# time-circuits.net
KiCad netlist of a schematic drawn in EAGLE
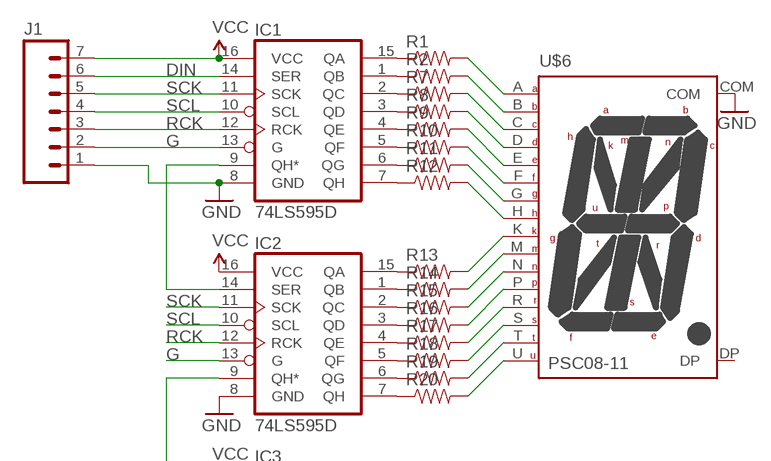
[diagram p0: schematic, sheet 1, part 1 of 2]
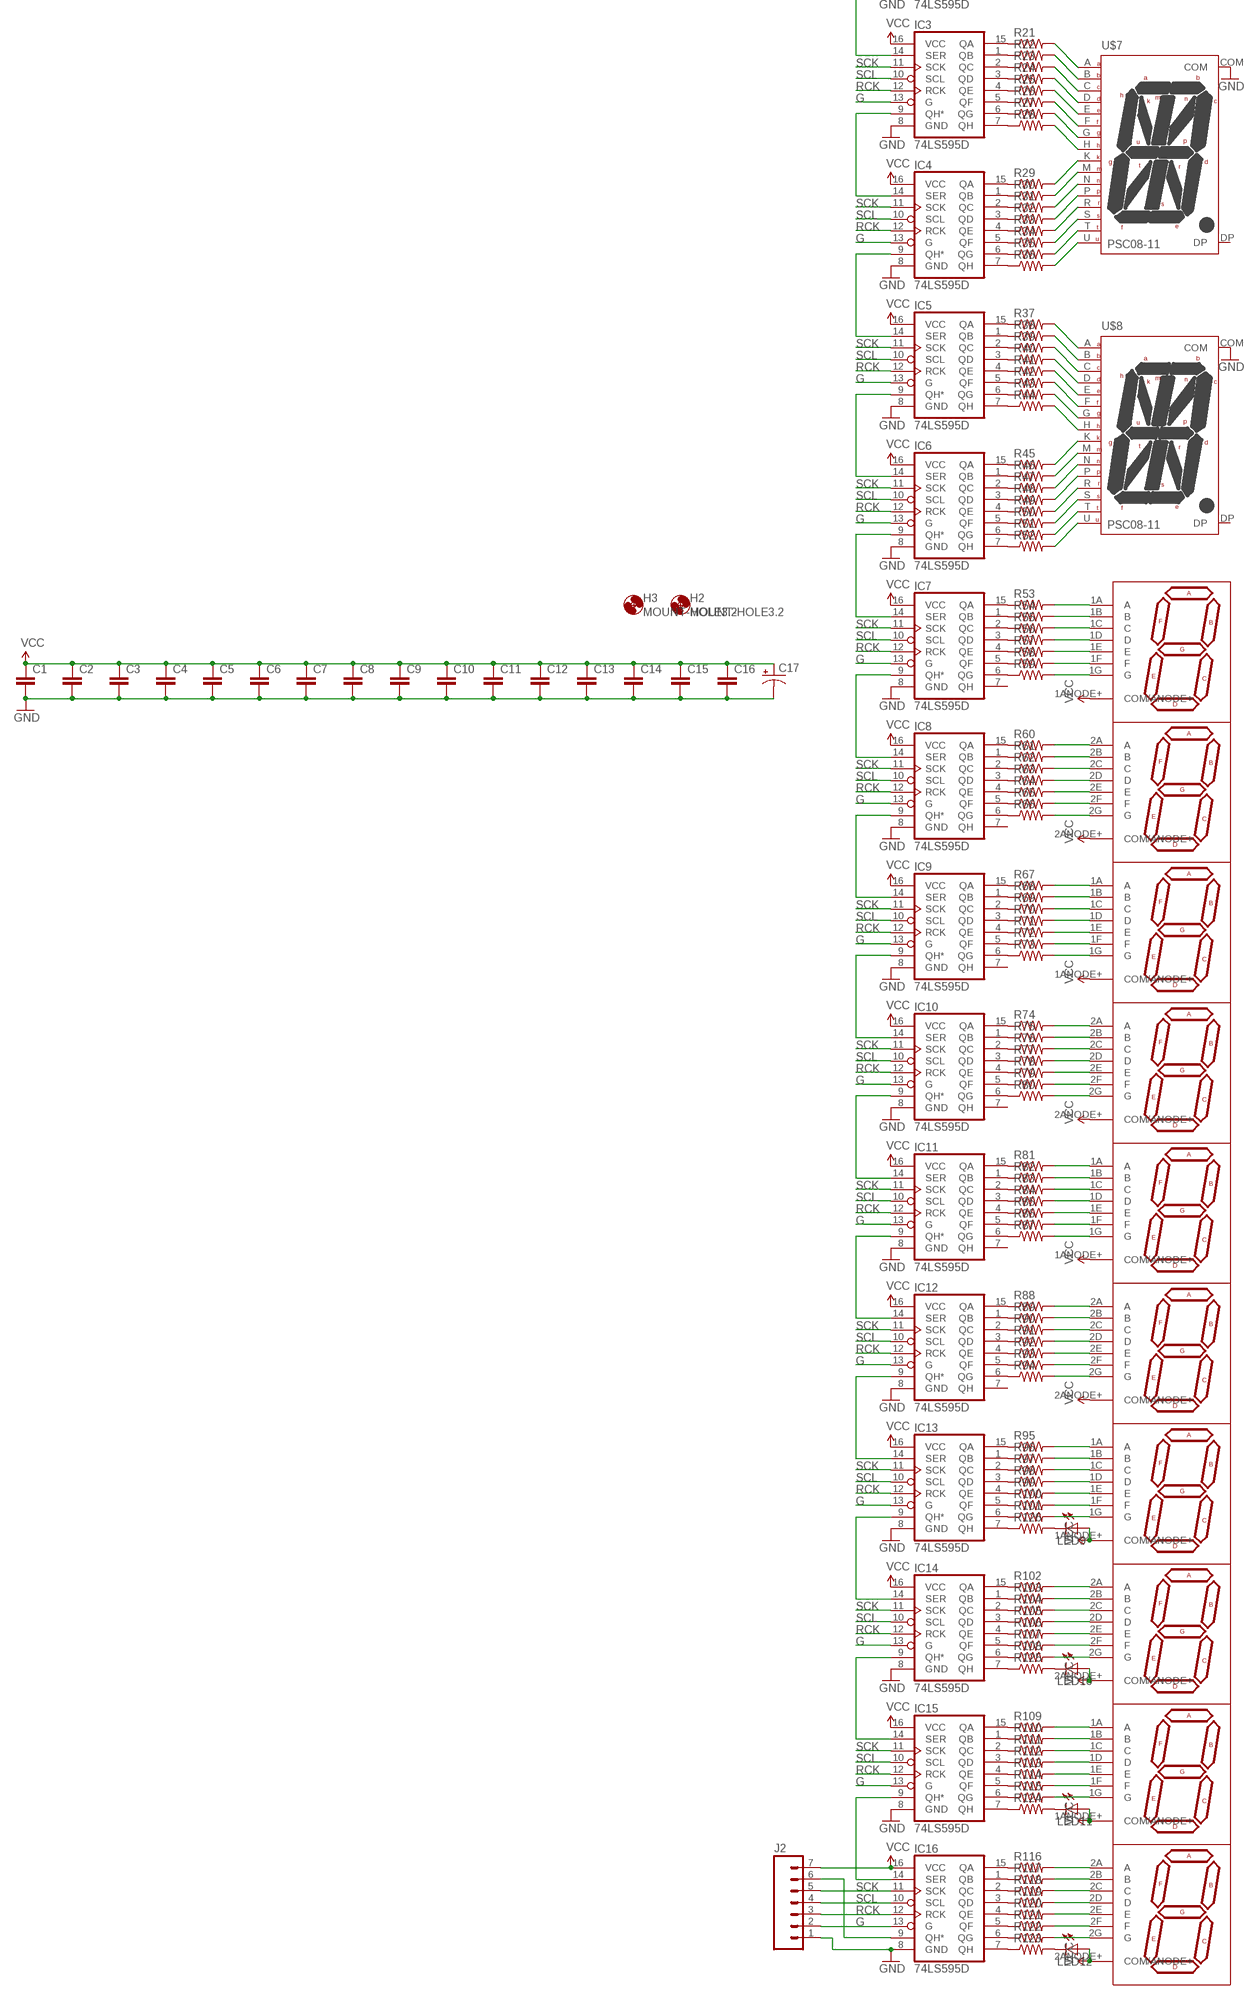
[diagram p1: schematic, sheet 1, part 2 of 2]

(export (version "E")
  (design (tool "Eeschema 10.0.6"))
  (components
    (comp (ref "C1")
      (value "CAP0805")
      (footprint "eagle-import:0805")
      (libsource (lib "eagle-import") (part "CAP0805"))
    )
    (comp (ref "C2")
      (value "CAP0805")
      (footprint "eagle-import:0805")
      (libsource (lib "eagle-import") (part "CAP0805"))
    )
    (comp (ref "C3")
      (value "CAP0805")
      (footprint "eagle-import:0805")
      (libsource (lib "eagle-import") (part "CAP0805"))
    )
    (comp (ref "C4")
      (value "CAP0805")
      (footprint "eagle-import:0805")
      (libsource (lib "eagle-import") (part "CAP0805"))
    )
    (comp (ref "C5")
      (value "CAP0805")
      (footprint "eagle-import:0805")
      (libsource (lib "eagle-import") (part "CAP0805"))
    )
    (comp (ref "C6")
      (value "CAP0805")
      (footprint "eagle-import:0805")
      (libsource (lib "eagle-import") (part "CAP0805"))
    )
    (comp (ref "C7")
      (value "CAP0805")
      (footprint "eagle-import:0805")
      (libsource (lib "eagle-import") (part "CAP0805"))
    )
    (comp (ref "C8")
      (value "CAP0805")
      (footprint "eagle-import:0805")
      (libsource (lib "eagle-import") (part "CAP0805"))
    )
    (comp (ref "C9")
      (value "CAP0805")
      (footprint "eagle-import:0805")
      (libsource (lib "eagle-import") (part "CAP0805"))
    )
    (comp (ref "C10")
      (value "CAP0805")
      (footprint "eagle-import:0805")
      (libsource (lib "eagle-import") (part "CAP0805"))
    )
    (comp (ref "C11")
      (value "CAP0805")
      (footprint "eagle-import:0805")
      (libsource (lib "eagle-import") (part "CAP0805"))
    )
    (comp (ref "C12")
      (value "CAP0805")
      (footprint "eagle-import:0805")
      (libsource (lib "eagle-import") (part "CAP0805"))
    )
    (comp (ref "C13")
      (value "CAP0805")
      (footprint "eagle-import:0805")
      (libsource (lib "eagle-import") (part "CAP0805"))
    )
    (comp (ref "C14")
      (value "CAP0805")
      (footprint "eagle-import:0805")
      (libsource (lib "eagle-import") (part "CAP0805"))
    )
    (comp (ref "C15")
      (value "CAP0805")
      (footprint "eagle-import:0805")
      (libsource (lib "eagle-import") (part "CAP0805"))
    )
    (comp (ref "C16")
      (value "CAP0805")
      (footprint "eagle-import:0805")
      (libsource (lib "eagle-import") (part "CAP0805"))
    )
    (comp (ref "C17")
      (value "CAP_POLH13")
      (footprint "eagle-import:PANASONIC_H13")
      (libsource (lib "eagle-import") (part "CAP_POLH13"))
    )
    (comp (ref "H2")
      (value "MOUNT-HOLE3.2")
      (footprint "eagle-import:3,2")
      (libsource (lib "eagle-import") (part "MOUNT-HOLE3.2"))
    )
    (comp (ref "H3")
      (value "MOUNT-HOLE3.2")
      (footprint "eagle-import:3,2")
      (libsource (lib "eagle-import") (part "MOUNT-HOLE3.2"))
    )
    (comp (ref "IC1")
      (value "74LS595D")
      (footprint "eagle-import:SO16")
      (libsource (lib "eagle-import") (part "74595DLS"))
    )
    (comp (ref "IC2")
      (value "74LS595D")
      (footprint "eagle-import:SO16")
      (libsource (lib "eagle-import") (part "74595DLS"))
    )
    (comp (ref "IC3")
      (value "74LS595D")
      (footprint "eagle-import:SO16")
      (libsource (lib "eagle-import") (part "74595DLS"))
    )
    (comp (ref "IC4")
      (value "74LS595D")
      (footprint "eagle-import:SO16")
      (libsource (lib "eagle-import") (part "74595DLS"))
    )
    (comp (ref "IC5")
      (value "74LS595D")
      (footprint "eagle-import:SO16")
      (libsource (lib "eagle-import") (part "74595DLS"))
    )
    (comp (ref "IC6")
      (value "74LS595D")
      (footprint "eagle-import:SO16")
      (libsource (lib "eagle-import") (part "74595DLS"))
    )
    (comp (ref "IC7")
      (value "74LS595D")
      (footprint "eagle-import:SO16")
      (libsource (lib "eagle-import") (part "74595DLS"))
    )
    (comp (ref "IC8")
      (value "74LS595D")
      (footprint "eagle-import:SO16")
      (libsource (lib "eagle-import") (part "74595DLS"))
    )
    (comp (ref "IC9")
      (value "74LS595D")
      (footprint "eagle-import:SO16")
      (libsource (lib "eagle-import") (part "74595DLS"))
    )
    (comp (ref "IC10")
      (value "74LS595D")
      (footprint "eagle-import:SO16")
      (libsource (lib "eagle-import") (part "74595DLS"))
    )
    (comp (ref "IC11")
      (value "74LS595D")
      (footprint "eagle-import:SO16")
      (libsource (lib "eagle-import") (part "74595DLS"))
    )
    (comp (ref "IC12")
      (value "74LS595D")
      (footprint "eagle-import:SO16")
      (libsource (lib "eagle-import") (part "74595DLS"))
    )
    (comp (ref "IC13")
      (value "74LS595D")
      (footprint "eagle-import:SO16")
      (libsource (lib "eagle-import") (part "74595DLS"))
    )
    (comp (ref "IC14")
      (value "74LS595D")
      (footprint "eagle-import:SO16")
      (libsource (lib "eagle-import") (part "74595DLS"))
    )
    (comp (ref "IC15")
      (value "74LS595D")
      (footprint "eagle-import:SO16")
      (libsource (lib "eagle-import") (part "74595DLS"))
    )
    (comp (ref "IC16")
      (value "74LS595D")
      (footprint "eagle-import:SO16")
      (libsource (lib "eagle-import") (part "74595DLS"))
    )
    (comp (ref "J1")
      (value "M07LOCK")
      (footprint "eagle-import:1X07_LOCK")
      (libsource (lib "eagle-import") (part "M07LOCK"))
    )
    (comp (ref "J2")
      (value "M07LOCK")
      (footprint "eagle-import:1X07_LOCK")
      (libsource (lib "eagle-import") (part "M07LOCK"))
    )
    (comp (ref "LED9")
      (value "LED5MM")
      (footprint "eagle-import:LED5MM")
      (libsource (lib "eagle-import") (part "LED5MM"))
    )
    (comp (ref "LED10")
      (value "LED5MM")
      (footprint "eagle-import:LED5MM")
      (libsource (lib "eagle-import") (part "LED5MM"))
    )
    (comp (ref "LED11")
      (value "LED5MM")
      (footprint "eagle-import:LED5MM")
      (libsource (lib "eagle-import") (part "LED5MM"))
    )
    (comp (ref "LED12")
      (value "LED5MM")
      (footprint "eagle-import:LED5MM")
      (libsource (lib "eagle-import") (part "LED5MM"))
    )
    (comp (ref "R1")
      (value "RESISTOR0805-RES")
      (footprint "eagle-import:0805")
      (libsource (lib "eagle-import") (part "RESISTOR0805-RES"))
    )
    (comp (ref "R2")
      (value "RESISTOR0805-RES")
      (footprint "eagle-import:0805")
      (libsource (lib "eagle-import") (part "RESISTOR0805-RES"))
    )
    (comp (ref "R7")
      (value "RESISTOR0805-RES")
      (footprint "eagle-import:0805")
      (libsource (lib "eagle-import") (part "RESISTOR0805-RES"))
    )
    (comp (ref "R8")
      (value "RESISTOR0805-RES")
      (footprint "eagle-import:0805")
      (libsource (lib "eagle-import") (part "RESISTOR0805-RES"))
    )
    (comp (ref "R9")
      (value "RESISTOR0805-RES")
      (footprint "eagle-import:0805")
      (libsource (lib "eagle-import") (part "RESISTOR0805-RES"))
    )
    (comp (ref "R10")
      (value "RESISTOR0805-RES")
      (footprint "eagle-import:0805")
      (libsource (lib "eagle-import") (part "RESISTOR0805-RES"))
    )
    (comp (ref "R11")
      (value "RESISTOR0805-RES")
      (footprint "eagle-import:0805")
      (libsource (lib "eagle-import") (part "RESISTOR0805-RES"))
    )
    (comp (ref "R12")
      (value "RESISTOR0805-RES")
      (footprint "eagle-import:0805")
      (libsource (lib "eagle-import") (part "RESISTOR0805-RES"))
    )
    (comp (ref "R13")
      (value "RESISTOR0805-RES")
      (footprint "eagle-import:0805")
      (libsource (lib "eagle-import") (part "RESISTOR0805-RES"))
    )
    (comp (ref "R14")
      (value "RESISTOR0805-RES")
      (footprint "eagle-import:0805")
      (libsource (lib "eagle-import") (part "RESISTOR0805-RES"))
    )
    (comp (ref "R15")
      (value "RESISTOR0805-RES")
      (footprint "eagle-import:0805")
      (libsource (lib "eagle-import") (part "RESISTOR0805-RES"))
    )
    (comp (ref "R16")
      (value "RESISTOR0805-RES")
      (footprint "eagle-import:0805")
      (libsource (lib "eagle-import") (part "RESISTOR0805-RES"))
    )
    (comp (ref "R17")
      (value "RESISTOR0805-RES")
      (footprint "eagle-import:0805")
      (libsource (lib "eagle-import") (part "RESISTOR0805-RES"))
    )
    (comp (ref "R18")
      (value "RESISTOR0805-RES")
      (footprint "eagle-import:0805")
      (libsource (lib "eagle-import") (part "RESISTOR0805-RES"))
    )
    (comp (ref "R19")
      (value "RESISTOR0805-RES")
      (footprint "eagle-import:0805")
      (libsource (lib "eagle-import") (part "RESISTOR0805-RES"))
    )
    (comp (ref "R20")
      (value "RESISTOR0805-RES")
      (footprint "eagle-import:0805")
      (libsource (lib "eagle-import") (part "RESISTOR0805-RES"))
    )
    (comp (ref "R21")
      (value "RESISTOR0805-RES")
      (footprint "eagle-import:0805")
      (libsource (lib "eagle-import") (part "RESISTOR0805-RES"))
    )
    (comp (ref "R22")
      (value "RESISTOR0805-RES")
      (footprint "eagle-import:0805")
      (libsource (lib "eagle-import") (part "RESISTOR0805-RES"))
    )
    (comp (ref "R23")
      (value "RESISTOR0805-RES")
      (footprint "eagle-import:0805")
      (libsource (lib "eagle-import") (part "RESISTOR0805-RES"))
    )
    (comp (ref "R24")
      (value "RESISTOR0805-RES")
      (footprint "eagle-import:0805")
      (libsource (lib "eagle-import") (part "RESISTOR0805-RES"))
    )
    (comp (ref "R25")
      (value "RESISTOR0805-RES")
      (footprint "eagle-import:0805")
      (libsource (lib "eagle-import") (part "RESISTOR0805-RES"))
    )
    (comp (ref "R26")
      (value "RESISTOR0805-RES")
      (footprint "eagle-import:0805")
      (libsource (lib "eagle-import") (part "RESISTOR0805-RES"))
    )
    (comp (ref "R27")
      (value "RESISTOR0805-RES")
      (footprint "eagle-import:0805")
      (libsource (lib "eagle-import") (part "RESISTOR0805-RES"))
    )
    (comp (ref "R28")
      (value "RESISTOR0805-RES")
      (footprint "eagle-import:0805")
      (libsource (lib "eagle-import") (part "RESISTOR0805-RES"))
    )
    (comp (ref "R29")
      (value "RESISTOR0805-RES")
      (footprint "eagle-import:0805")
      (libsource (lib "eagle-import") (part "RESISTOR0805-RES"))
    )
    (comp (ref "R30")
      (value "RESISTOR0805-RES")
      (footprint "eagle-import:0805")
      (libsource (lib "eagle-import") (part "RESISTOR0805-RES"))
    )
    (comp (ref "R31")
      (value "RESISTOR0805-RES")
      (footprint "eagle-import:0805")
      (libsource (lib "eagle-import") (part "RESISTOR0805-RES"))
    )
    (comp (ref "R32")
      (value "RESISTOR0805-RES")
      (footprint "eagle-import:0805")
      (libsource (lib "eagle-import") (part "RESISTOR0805-RES"))
    )
    (comp (ref "R33")
      (value "RESISTOR0805-RES")
      (footprint "eagle-import:0805")
      (libsource (lib "eagle-import") (part "RESISTOR0805-RES"))
    )
    (comp (ref "R34")
      (value "RESISTOR0805-RES")
      (footprint "eagle-import:0805")
      (libsource (lib "eagle-import") (part "RESISTOR0805-RES"))
    )
    (comp (ref "R35")
      (value "RESISTOR0805-RES")
      (footprint "eagle-import:0805")
      (libsource (lib "eagle-import") (part "RESISTOR0805-RES"))
    )
    (comp (ref "R36")
      (value "RESISTOR0805-RES")
      (footprint "eagle-import:0805")
      (libsource (lib "eagle-import") (part "RESISTOR0805-RES"))
    )
    (comp (ref "R37")
      (value "RESISTOR0805-RES")
      (footprint "eagle-import:0805")
      (libsource (lib "eagle-import") (part "RESISTOR0805-RES"))
    )
    (comp (ref "R38")
      (value "RESISTOR0805-RES")
      (footprint "eagle-import:0805")
      (libsource (lib "eagle-import") (part "RESISTOR0805-RES"))
    )
    (comp (ref "R39")
      (value "RESISTOR0805-RES")
      (footprint "eagle-import:0805")
      (libsource (lib "eagle-import") (part "RESISTOR0805-RES"))
    )
    (comp (ref "R40")
      (value "RESISTOR0805-RES")
      (footprint "eagle-import:0805")
      (libsource (lib "eagle-import") (part "RESISTOR0805-RES"))
    )
    (comp (ref "R41")
      (value "RESISTOR0805-RES")
      (footprint "eagle-import:0805")
      (libsource (lib "eagle-import") (part "RESISTOR0805-RES"))
    )
    (comp (ref "R42")
      (value "RESISTOR0805-RES")
      (footprint "eagle-import:0805")
      (libsource (lib "eagle-import") (part "RESISTOR0805-RES"))
    )
    (comp (ref "R43")
      (value "RESISTOR0805-RES")
      (footprint "eagle-import:0805")
      (libsource (lib "eagle-import") (part "RESISTOR0805-RES"))
    )
    (comp (ref "R44")
      (value "RESISTOR0805-RES")
      (footprint "eagle-import:0805")
      (libsource (lib "eagle-import") (part "RESISTOR0805-RES"))
    )
    (comp (ref "R45")
      (value "RESISTOR0805-RES")
      (footprint "eagle-import:0805")
      (libsource (lib "eagle-import") (part "RESISTOR0805-RES"))
    )
    (comp (ref "R46")
      (value "RESISTOR0805-RES")
      (footprint "eagle-import:0805")
      (libsource (lib "eagle-import") (part "RESISTOR0805-RES"))
    )
    (comp (ref "R47")
      (value "RESISTOR0805-RES")
      (footprint "eagle-import:0805")
      (libsource (lib "eagle-import") (part "RESISTOR0805-RES"))
    )
    (comp (ref "R48")
      (value "RESISTOR0805-RES")
      (footprint "eagle-import:0805")
      (libsource (lib "eagle-import") (part "RESISTOR0805-RES"))
    )
    (comp (ref "R49")
      (value "RESISTOR0805-RES")
      (footprint "eagle-import:0805")
      (libsource (lib "eagle-import") (part "RESISTOR0805-RES"))
    )
    (comp (ref "R50")
      (value "RESISTOR0805-RES")
      (footprint "eagle-import:0805")
      (libsource (lib "eagle-import") (part "RESISTOR0805-RES"))
    )
    (comp (ref "R51")
      (value "RESISTOR0805-RES")
      (footprint "eagle-import:0805")
      (libsource (lib "eagle-import") (part "RESISTOR0805-RES"))
    )
    (comp (ref "R52")
      (value "RESISTOR0805-RES")
      (footprint "eagle-import:0805")
      (libsource (lib "eagle-import") (part "RESISTOR0805-RES"))
    )
    (comp (ref "R53")
      (value "RESISTOR0805-RES")
      (footprint "eagle-import:0805")
      (libsource (lib "eagle-import") (part "RESISTOR0805-RES"))
    )
    (comp (ref "R54")
      (value "RESISTOR0805-RES")
      (footprint "eagle-import:0805")
      (libsource (lib "eagle-import") (part "RESISTOR0805-RES"))
    )
    (comp (ref "R55")
      (value "RESISTOR0805-RES")
      (footprint "eagle-import:0805")
      (libsource (lib "eagle-import") (part "RESISTOR0805-RES"))
    )
    (comp (ref "R56")
      (value "RESISTOR0805-RES")
      (footprint "eagle-import:0805")
      (libsource (lib "eagle-import") (part "RESISTOR0805-RES"))
    )
    (comp (ref "R57")
      (value "RESISTOR0805-RES")
      (footprint "eagle-import:0805")
      (libsource (lib "eagle-import") (part "RESISTOR0805-RES"))
    )
    (comp (ref "R58")
      (value "RESISTOR0805-RES")
      (footprint "eagle-import:0805")
      (libsource (lib "eagle-import") (part "RESISTOR0805-RES"))
    )
    (comp (ref "R59")
      (value "RESISTOR0805-RES")
      (footprint "eagle-import:0805")
      (libsource (lib "eagle-import") (part "RESISTOR0805-RES"))
    )
    (comp (ref "R60")
      (value "RESISTOR0805-RES")
      (footprint "eagle-import:0805")
      (libsource (lib "eagle-import") (part "RESISTOR0805-RES"))
    )
    (comp (ref "R61")
      (value "RESISTOR0805-RES")
      (footprint "eagle-import:0805")
      (libsource (lib "eagle-import") (part "RESISTOR0805-RES"))
    )
    (comp (ref "R62")
      (value "RESISTOR0805-RES")
      (footprint "eagle-import:0805")
      (libsource (lib "eagle-import") (part "RESISTOR0805-RES"))
    )
    (comp (ref "R63")
      (value "RESISTOR0805-RES")
      (footprint "eagle-import:0805")
      (libsource (lib "eagle-import") (part "RESISTOR0805-RES"))
    )
    (comp (ref "R64")
      (value "RESISTOR0805-RES")
      (footprint "eagle-import:0805")
      (libsource (lib "eagle-import") (part "RESISTOR0805-RES"))
    )
    (comp (ref "R65")
      (value "RESISTOR0805-RES")
      (footprint "eagle-import:0805")
      (libsource (lib "eagle-import") (part "RESISTOR0805-RES"))
    )
    (comp (ref "R66")
      (value "RESISTOR0805-RES")
      (footprint "eagle-import:0805")
      (libsource (lib "eagle-import") (part "RESISTOR0805-RES"))
    )
    (comp (ref "R67")
      (value "RESISTOR0805-RES")
      (footprint "eagle-import:0805")
      (libsource (lib "eagle-import") (part "RESISTOR0805-RES"))
    )
    (comp (ref "R68")
      (value "RESISTOR0805-RES")
      (footprint "eagle-import:0805")
      (libsource (lib "eagle-import") (part "RESISTOR0805-RES"))
    )
    (comp (ref "R69")
      (value "RESISTOR0805-RES")
      (footprint "eagle-import:0805")
      (libsource (lib "eagle-import") (part "RESISTOR0805-RES"))
    )
    (comp (ref "R70")
      (value "RESISTOR0805-RES")
      (footprint "eagle-import:0805")
      (libsource (lib "eagle-import") (part "RESISTOR0805-RES"))
    )
    (comp (ref "R71")
      (value "RESISTOR0805-RES")
      (footprint "eagle-import:0805")
      (libsource (lib "eagle-import") (part "RESISTOR0805-RES"))
    )
    (comp (ref "R72")
      (value "RESISTOR0805-RES")
      (footprint "eagle-import:0805")
      (libsource (lib "eagle-import") (part "RESISTOR0805-RES"))
    )
    (comp (ref "R73")
      (value "RESISTOR0805-RES")
      (footprint "eagle-import:0805")
      (libsource (lib "eagle-import") (part "RESISTOR0805-RES"))
    )
    (comp (ref "R74")
      (value "RESISTOR0805-RES")
      (footprint "eagle-import:0805")
      (libsource (lib "eagle-import") (part "RESISTOR0805-RES"))
    )
    (comp (ref "R75")
      (value "RESISTOR0805-RES")
      (footprint "eagle-import:0805")
      (libsource (lib "eagle-import") (part "RESISTOR0805-RES"))
    )
    (comp (ref "R76")
      (value "RESISTOR0805-RES")
      (footprint "eagle-import:0805")
      (libsource (lib "eagle-import") (part "RESISTOR0805-RES"))
    )
    (comp (ref "R77")
      (value "RESISTOR0805-RES")
      (footprint "eagle-import:0805")
      (libsource (lib "eagle-import") (part "RESISTOR0805-RES"))
    )
    (comp (ref "R78")
      (value "RESISTOR0805-RES")
      (footprint "eagle-import:0805")
      (libsource (lib "eagle-import") (part "RESISTOR0805-RES"))
    )
    (comp (ref "R79")
      (value "RESISTOR0805-RES")
      (footprint "eagle-import:0805")
      (libsource (lib "eagle-import") (part "RESISTOR0805-RES"))
    )
    (comp (ref "R80")
      (value "RESISTOR0805-RES")
      (footprint "eagle-import:0805")
      (libsource (lib "eagle-import") (part "RESISTOR0805-RES"))
    )
    (comp (ref "R81")
      (value "RESISTOR0805-RES")
      (footprint "eagle-import:0805")
      (libsource (lib "eagle-import") (part "RESISTOR0805-RES"))
    )
    (comp (ref "R82")
      (value "RESISTOR0805-RES")
      (footprint "eagle-import:0805")
      (libsource (lib "eagle-import") (part "RESISTOR0805-RES"))
    )
    (comp (ref "R83")
      (value "RESISTOR0805-RES")
      (footprint "eagle-import:0805")
      (libsource (lib "eagle-import") (part "RESISTOR0805-RES"))
    )
    (comp (ref "R84")
      (value "RESISTOR0805-RES")
      (footprint "eagle-import:0805")
      (libsource (lib "eagle-import") (part "RESISTOR0805-RES"))
    )
    (comp (ref "R85")
      (value "RESISTOR0805-RES")
      (footprint "eagle-import:0805")
      (libsource (lib "eagle-import") (part "RESISTOR0805-RES"))
    )
    (comp (ref "R86")
      (value "RESISTOR0805-RES")
      (footprint "eagle-import:0805")
      (libsource (lib "eagle-import") (part "RESISTOR0805-RES"))
    )
    (comp (ref "R87")
      (value "RESISTOR0805-RES")
      (footprint "eagle-import:0805")
      (libsource (lib "eagle-import") (part "RESISTOR0805-RES"))
    )
    (comp (ref "R88")
      (value "RESISTOR0805-RES")
      (footprint "eagle-import:0805")
      (libsource (lib "eagle-import") (part "RESISTOR0805-RES"))
    )
    (comp (ref "R89")
      (value "RESISTOR0805-RES")
      (footprint "eagle-import:0805")
      (libsource (lib "eagle-import") (part "RESISTOR0805-RES"))
    )
    (comp (ref "R90")
      (value "RESISTOR0805-RES")
      (footprint "eagle-import:0805")
      (libsource (lib "eagle-import") (part "RESISTOR0805-RES"))
    )
    (comp (ref "R91")
      (value "RESISTOR0805-RES")
      (footprint "eagle-import:0805")
      (libsource (lib "eagle-import") (part "RESISTOR0805-RES"))
    )
    (comp (ref "R92")
      (value "RESISTOR0805-RES")
      (footprint "eagle-import:0805")
      (libsource (lib "eagle-import") (part "RESISTOR0805-RES"))
    )
    (comp (ref "R93")
      (value "RESISTOR0805-RES")
      (footprint "eagle-import:0805")
      (libsource (lib "eagle-import") (part "RESISTOR0805-RES"))
    )
    (comp (ref "R94")
      (value "RESISTOR0805-RES")
      (footprint "eagle-import:0805")
      (libsource (lib "eagle-import") (part "RESISTOR0805-RES"))
    )
    (comp (ref "R95")
      (value "RESISTOR0805-RES")
      (footprint "eagle-import:0805")
      (libsource (lib "eagle-import") (part "RESISTOR0805-RES"))
    )
    (comp (ref "R96")
      (value "RESISTOR0805-RES")
      (footprint "eagle-import:0805")
      (libsource (lib "eagle-import") (part "RESISTOR0805-RES"))
    )
    (comp (ref "R97")
      (value "RESISTOR0805-RES")
      (footprint "eagle-import:0805")
      (libsource (lib "eagle-import") (part "RESISTOR0805-RES"))
    )
    (comp (ref "R98")
      (value "RESISTOR0805-RES")
      (footprint "eagle-import:0805")
      (libsource (lib "eagle-import") (part "RESISTOR0805-RES"))
    )
    (comp (ref "R99")
      (value "RESISTOR0805-RES")
      (footprint "eagle-import:0805")
      (libsource (lib "eagle-import") (part "RESISTOR0805-RES"))
    )
    (comp (ref "R100")
      (value "RESISTOR0805-RES")
      (footprint "eagle-import:0805")
      (libsource (lib "eagle-import") (part "RESISTOR0805-RES"))
    )
    (comp (ref "R101")
      (value "RESISTOR0805-RES")
      (footprint "eagle-import:0805")
      (libsource (lib "eagle-import") (part "RESISTOR0805-RES"))
    )
    (comp (ref "R102")
      (value "RESISTOR0805-RES")
      (footprint "eagle-import:0805")
      (libsource (lib "eagle-import") (part "RESISTOR0805-RES"))
    )
    (comp (ref "R103")
      (value "RESISTOR0805-RES")
      (footprint "eagle-import:0805")
      (libsource (lib "eagle-import") (part "RESISTOR0805-RES"))
    )
    (comp (ref "R104")
      (value "RESISTOR0805-RES")
      (footprint "eagle-import:0805")
      (libsource (lib "eagle-import") (part "RESISTOR0805-RES"))
    )
    (comp (ref "R105")
      (value "RESISTOR0805-RES")
      (footprint "eagle-import:0805")
      (libsource (lib "eagle-import") (part "RESISTOR0805-RES"))
    )
    (comp (ref "R106")
      (value "RESISTOR0805-RES")
      (footprint "eagle-import:0805")
      (libsource (lib "eagle-import") (part "RESISTOR0805-RES"))
    )
    (comp (ref "R107")
      (value "RESISTOR0805-RES")
      (footprint "eagle-import:0805")
      (libsource (lib "eagle-import") (part "RESISTOR0805-RES"))
    )
    (comp (ref "R108")
      (value "RESISTOR0805-RES")
      (footprint "eagle-import:0805")
      (libsource (lib "eagle-import") (part "RESISTOR0805-RES"))
    )
    (comp (ref "R109")
      (value "RESISTOR0805-RES")
      (footprint "eagle-import:0805")
      (libsource (lib "eagle-import") (part "RESISTOR0805-RES"))
    )
    (comp (ref "R110")
      (value "RESISTOR0805-RES")
      (footprint "eagle-import:0805")
      (libsource (lib "eagle-import") (part "RESISTOR0805-RES"))
    )
    (comp (ref "R111")
      (value "RESISTOR0805-RES")
      (footprint "eagle-import:0805")
      (libsource (lib "eagle-import") (part "RESISTOR0805-RES"))
    )
    (comp (ref "R112")
      (value "RESISTOR0805-RES")
      (footprint "eagle-import:0805")
      (libsource (lib "eagle-import") (part "RESISTOR0805-RES"))
    )
    (comp (ref "R113")
      (value "RESISTOR0805-RES")
      (footprint "eagle-import:0805")
      (libsource (lib "eagle-import") (part "RESISTOR0805-RES"))
    )
    (comp (ref "R114")
      (value "RESISTOR0805-RES")
      (footprint "eagle-import:0805")
      (libsource (lib "eagle-import") (part "RESISTOR0805-RES"))
    )
    (comp (ref "R115")
      (value "RESISTOR0805-RES")
      (footprint "eagle-import:0805")
      (libsource (lib "eagle-import") (part "RESISTOR0805-RES"))
    )
    (comp (ref "R116")
      (value "RESISTOR0805-RES")
      (footprint "eagle-import:0805")
      (libsource (lib "eagle-import") (part "RESISTOR0805-RES"))
    )
    (comp (ref "R117")
      (value "RESISTOR0805-RES")
      (footprint "eagle-import:0805")
      (libsource (lib "eagle-import") (part "RESISTOR0805-RES"))
    )
    (comp (ref "R118")
      (value "RESISTOR0805-RES")
      (footprint "eagle-import:0805")
      (libsource (lib "eagle-import") (part "RESISTOR0805-RES"))
    )
    (comp (ref "R119")
      (value "RESISTOR0805-RES")
      (footprint "eagle-import:0805")
      (libsource (lib "eagle-import") (part "RESISTOR0805-RES"))
    )
    (comp (ref "R120")
      (value "RESISTOR0805-RES")
      (footprint "eagle-import:0805")
      (libsource (lib "eagle-import") (part "RESISTOR0805-RES"))
    )
    (comp (ref "R121")
      (value "RESISTOR0805-RES")
      (footprint "eagle-import:0805")
      (libsource (lib "eagle-import") (part "RESISTOR0805-RES"))
    )
    (comp (ref "R122")
      (value "RESISTOR0805-RES")
      (footprint "eagle-import:0805")
      (libsource (lib "eagle-import") (part "RESISTOR0805-RES"))
    )
    (comp (ref "R123")
      (value "RESISTOR0805-RES")
      (footprint "eagle-import:0805")
      (libsource (lib "eagle-import") (part "RESISTOR0805-RES"))
    )
    (comp (ref "R124")
      (value "RESISTOR0805-RES")
      (footprint "eagle-import:0805")
      (libsource (lib "eagle-import") (part "RESISTOR0805-RES"))
    )
    (comp (ref "R125")
      (value "RESISTOR0805-RES")
      (footprint "eagle-import:0805")
      (libsource (lib "eagle-import") (part "RESISTOR0805-RES"))
    )
    (comp (ref "R126")
      (value "RESISTOR0805-RES")
      (footprint "eagle-import:0805")
      (libsource (lib "eagle-import") (part "RESISTOR0805-RES"))
    )
    (comp (ref "U$1")
      (value "DA08-11")
      (footprint "eagle-import:DA08-11")
      (libsource (lib "eagle-import") (part "DA08-11"))
    )
    (comp (ref "U$2")
      (value "DA08-11")
      (footprint "eagle-import:DA08-11")
      (libsource (lib "eagle-import") (part "DA08-11"))
    )
    (comp (ref "U$3")
      (value "DA08-11")
      (footprint "eagle-import:DA08-11")
      (libsource (lib "eagle-import") (part "DA08-11"))
    )
    (comp (ref "U$4")
      (value "DA08-11")
      (footprint "eagle-import:DA08-11")
      (libsource (lib "eagle-import") (part "DA08-11"))
    )
    (comp (ref "U$5")
      (value "DA08-11")
      (footprint "eagle-import:DA08-11")
      (libsource (lib "eagle-import") (part "DA08-11"))
    )
    (comp (ref "U$6")
      (value "PSC08-11")
      (footprint "eagle-import:PSC08-11")
      (libsource (lib "eagle-import") (part "PSC08-11"))
    )
    (comp (ref "U$7")
      (value "PSC08-11")
      (footprint "eagle-import:PSC08-11")
      (libsource (lib "eagle-import") (part "PSC08-11"))
    )
    (comp (ref "U$8")
      (value "PSC08-11")
      (footprint "eagle-import:PSC08-11")
      (libsource (lib "eagle-import") (part "PSC08-11"))
    )
  )
  (nets
    (net (code "1") (name "/DIN") (class "Default")
      (node (ref "IC1") (pin "14") (pinfunction "SER_14") (pintype "input"))
      (node (ref "J1") (pin "6") (pinfunction "6_6") (pintype "passive"))
    )
    (net (code "2") (name "/G") (class "Default")
      (node (ref "IC1") (pin "13") (pinfunction "G_13") (pintype "input"))
      (node (ref "IC10") (pin "13") (pinfunction "G_13") (pintype "input"))
      (node (ref "IC11") (pin "13") (pinfunction "G_13") (pintype "input"))
      (node (ref "IC12") (pin "13") (pinfunction "G_13") (pintype "input"))
      (node (ref "IC13") (pin "13") (pinfunction "G_13") (pintype "input"))
      (node (ref "IC14") (pin "13") (pinfunction "G_13") (pintype "input"))
      (node (ref "IC15") (pin "13") (pinfunction "G_13") (pintype "input"))
      (node (ref "IC16") (pin "13") (pinfunction "G_13") (pintype "input"))
      (node (ref "IC2") (pin "13") (pinfunction "G_13") (pintype "input"))
      (node (ref "IC3") (pin "13") (pinfunction "G_13") (pintype "input"))
      (node (ref "IC4") (pin "13") (pinfunction "G_13") (pintype "input"))
      (node (ref "IC5") (pin "13") (pinfunction "G_13") (pintype "input"))
      (node (ref "IC6") (pin "13") (pinfunction "G_13") (pintype "input"))
      (node (ref "IC7") (pin "13") (pinfunction "G_13") (pintype "input"))
      (node (ref "IC8") (pin "13") (pinfunction "G_13") (pintype "input"))
      (node (ref "IC9") (pin "13") (pinfunction "G_13") (pintype "input"))
      (node (ref "J1") (pin "2") (pinfunction "2_2") (pintype "passive"))
      (node (ref "J2") (pin "2") (pinfunction "2_2") (pintype "passive"))
    )
    (net (code "3") (name "/RCK") (class "Default")
      (node (ref "IC1") (pin "12") (pinfunction "RCK_12") (pintype "input"))
      (node (ref "IC10") (pin "12") (pinfunction "RCK_12") (pintype "input"))
      (node (ref "IC11") (pin "12") (pinfunction "RCK_12") (pintype "input"))
      (node (ref "IC12") (pin "12") (pinfunction "RCK_12") (pintype "input"))
      (node (ref "IC13") (pin "12") (pinfunction "RCK_12") (pintype "input"))
      (node (ref "IC14") (pin "12") (pinfunction "RCK_12") (pintype "input"))
      (node (ref "IC15") (pin "12") (pinfunction "RCK_12") (pintype "input"))
      (node (ref "IC16") (pin "12") (pinfunction "RCK_12") (pintype "input"))
      (node (ref "IC2") (pin "12") (pinfunction "RCK_12") (pintype "input"))
      (node (ref "IC3") (pin "12") (pinfunction "RCK_12") (pintype "input"))
      (node (ref "IC4") (pin "12") (pinfunction "RCK_12") (pintype "input"))
      (node (ref "IC5") (pin "12") (pinfunction "RCK_12") (pintype "input"))
      (node (ref "IC6") (pin "12") (pinfunction "RCK_12") (pintype "input"))
      (node (ref "IC7") (pin "12") (pinfunction "RCK_12") (pintype "input"))
      (node (ref "IC8") (pin "12") (pinfunction "RCK_12") (pintype "input"))
      (node (ref "IC9") (pin "12") (pinfunction "RCK_12") (pintype "input"))
      (node (ref "J1") (pin "3") (pinfunction "3_3") (pintype "passive"))
      (node (ref "J2") (pin "3") (pinfunction "3_3") (pintype "passive"))
    )
    (net (code "4") (name "/SCK") (class "Default")
      (node (ref "IC1") (pin "11") (pinfunction "SCK_11") (pintype "input"))
      (node (ref "IC10") (pin "11") (pinfunction "SCK_11") (pintype "input"))
      (node (ref "IC11") (pin "11") (pinfunction "SCK_11") (pintype "input"))
      (node (ref "IC12") (pin "11") (pinfunction "SCK_11") (pintype "input"))
      (node (ref "IC13") (pin "11") (pinfunction "SCK_11") (pintype "input"))
      (node (ref "IC14") (pin "11") (pinfunction "SCK_11") (pintype "input"))
      (node (ref "IC15") (pin "11") (pinfunction "SCK_11") (pintype "input"))
      (node (ref "IC16") (pin "11") (pinfunction "SCK_11") (pintype "input"))
      (node (ref "IC2") (pin "11") (pinfunction "SCK_11") (pintype "input"))
      (node (ref "IC3") (pin "11") (pinfunction "SCK_11") (pintype "input"))
      (node (ref "IC4") (pin "11") (pinfunction "SCK_11") (pintype "input"))
      (node (ref "IC5") (pin "11") (pinfunction "SCK_11") (pintype "input"))
      (node (ref "IC6") (pin "11") (pinfunction "SCK_11") (pintype "input"))
      (node (ref "IC7") (pin "11") (pinfunction "SCK_11") (pintype "input"))
      (node (ref "IC8") (pin "11") (pinfunction "SCK_11") (pintype "input"))
      (node (ref "IC9") (pin "11") (pinfunction "SCK_11") (pintype "input"))
      (node (ref "J1") (pin "5") (pinfunction "5_5") (pintype "passive"))
      (node (ref "J2") (pin "5") (pinfunction "5_5") (pintype "passive"))
    )
    (net (code "5") (name "/SCL") (class "Default")
      (node (ref "IC1") (pin "10") (pinfunction "SCL_10") (pintype "input"))
      (node (ref "IC10") (pin "10") (pinfunction "SCL_10") (pintype "input"))
      (node (ref "IC11") (pin "10") (pinfunction "SCL_10") (pintype "input"))
      (node (ref "IC12") (pin "10") (pinfunction "SCL_10") (pintype "input"))
      (node (ref "IC13") (pin "10") (pinfunction "SCL_10") (pintype "input"))
      (node (ref "IC14") (pin "10") (pinfunction "SCL_10") (pintype "input"))
      (node (ref "IC15") (pin "10") (pinfunction "SCL_10") (pintype "input"))
      (node (ref "IC16") (pin "10") (pinfunction "SCL_10") (pintype "input"))
      (node (ref "IC2") (pin "10") (pinfunction "SCL_10") (pintype "input"))
      (node (ref "IC3") (pin "10") (pinfunction "SCL_10") (pintype "input"))
      (node (ref "IC4") (pin "10") (pinfunction "SCL_10") (pintype "input"))
      (node (ref "IC5") (pin "10") (pinfunction "SCL_10") (pintype "input"))
      (node (ref "IC6") (pin "10") (pinfunction "SCL_10") (pintype "input"))
      (node (ref "IC7") (pin "10") (pinfunction "SCL_10") (pintype "input"))
      (node (ref "IC8") (pin "10") (pinfunction "SCL_10") (pintype "input"))
      (node (ref "IC9") (pin "10") (pinfunction "SCL_10") (pintype "input"))
      (node (ref "J1") (pin "4") (pinfunction "4_4") (pintype "passive"))
      (node (ref "J2") (pin "4") (pinfunction "4_4") (pintype "passive"))
    )
    (net (code "6") (name "GND") (class "Default")
      (node (ref "C1") (pin "2") (pinfunction "2_2") (pintype "passive"))
      (node (ref "C10") (pin "2") (pinfunction "2_2") (pintype "passive"))
      (node (ref "C11") (pin "2") (pinfunction "2_2") (pintype "passive"))
      (node (ref "C12") (pin "2") (pinfunction "2_2") (pintype "passive"))
      (node (ref "C13") (pin "2") (pinfunction "2_2") (pintype "passive"))
      (node (ref "C14") (pin "2") (pinfunction "2_2") (pintype "passive"))
      (node (ref "C15") (pin "2") (pinfunction "2_2") (pintype "passive"))
      (node (ref "C16") (pin "2") (pinfunction "2_2") (pintype "passive"))
      (node (ref "C17") (pin "-") (pinfunction "-_-") (pintype "passive"))
      (node (ref "C2") (pin "2") (pinfunction "2_2") (pintype "passive"))
      (node (ref "C3") (pin "2") (pinfunction "2_2") (pintype "passive"))
      (node (ref "C4") (pin "2") (pinfunction "2_2") (pintype "passive"))
      (node (ref "C5") (pin "2") (pinfunction "2_2") (pintype "passive"))
      (node (ref "C6") (pin "2") (pinfunction "2_2") (pintype "passive"))
      (node (ref "C7") (pin "2") (pinfunction "2_2") (pintype "passive"))
      (node (ref "C8") (pin "2") (pinfunction "2_2") (pintype "passive"))
      (node (ref "C9") (pin "2") (pinfunction "2_2") (pintype "passive"))
      (node (ref "IC1") (pin "8") (pinfunction "GND_8") (pintype "power_in"))
      (node (ref "IC10") (pin "8") (pinfunction "GND_8") (pintype "power_in"))
      (node (ref "IC11") (pin "8") (pinfunction "GND_8") (pintype "power_in"))
      (node (ref "IC12") (pin "8") (pinfunction "GND_8") (pintype "power_in"))
      (node (ref "IC13") (pin "8") (pinfunction "GND_8") (pintype "power_in"))
      (node (ref "IC14") (pin "8") (pinfunction "GND_8") (pintype "power_in"))
      (node (ref "IC15") (pin "8") (pinfunction "GND_8") (pintype "power_in"))
      (node (ref "IC16") (pin "8") (pinfunction "GND_8") (pintype "power_in"))
      (node (ref "IC2") (pin "8") (pinfunction "GND_8") (pintype "power_in"))
      (node (ref "IC3") (pin "8") (pinfunction "GND_8") (pintype "power_in"))
      (node (ref "IC4") (pin "8") (pinfunction "GND_8") (pintype "power_in"))
      (node (ref "IC5") (pin "8") (pinfunction "GND_8") (pintype "power_in"))
      (node (ref "IC6") (pin "8") (pinfunction "GND_8") (pintype "power_in"))
      (node (ref "IC7") (pin "8") (pinfunction "GND_8") (pintype "power_in"))
      (node (ref "IC8") (pin "8") (pinfunction "GND_8") (pintype "power_in"))
      (node (ref "IC9") (pin "8") (pinfunction "GND_8") (pintype "power_in"))
      (node (ref "J1") (pin "1") (pinfunction "1_1") (pintype "passive"))
      (node (ref "J2") (pin "1") (pinfunction "1_1") (pintype "passive"))
      (node (ref "U$6") (pin "COM") (pinfunction "COM_COM") (pintype "passive"))
      (node (ref "U$7") (pin "COM") (pinfunction "COM_COM") (pintype "passive"))
      (node (ref "U$8") (pin "COM") (pinfunction "COM_COM") (pintype "passive"))
    )
    (net (code "7") (name "Net-(IC1-QA)") (class "Default")
      (node (ref "IC1") (pin "15") (pinfunction "QA_15") (pintype "tri_state"))
      (node (ref "R1") (pin "1") (pinfunction "1_1") (pintype "passive"))
    )
    (net (code "8") (name "Net-(IC1-QB)") (class "Default")
      (node (ref "IC1") (pin "1") (pinfunction "QB_1") (pintype "tri_state"))
      (node (ref "R2") (pin "1") (pinfunction "1_1") (pintype "passive"))
    )
    (net (code "9") (name "Net-(IC1-QC)") (class "Default")
      (node (ref "IC1") (pin "2") (pinfunction "QC_2") (pintype "tri_state"))
      (node (ref "R7") (pin "1") (pinfunction "1_1") (pintype "passive"))
    )
    (net (code "10") (name "Net-(IC1-QD)") (class "Default")
      (node (ref "IC1") (pin "3") (pinfunction "QD_3") (pintype "tri_state"))
      (node (ref "R8") (pin "1") (pinfunction "1_1") (pintype "passive"))
    )
    (net (code "11") (name "Net-(IC1-QE)") (class "Default")
      (node (ref "IC1") (pin "4") (pinfunction "QE_4") (pintype "tri_state"))
      (node (ref "R9") (pin "1") (pinfunction "1_1") (pintype "passive"))
    )
    (net (code "12") (name "Net-(IC1-QF)") (class "Default")
      (node (ref "IC1") (pin "5") (pinfunction "QF_5") (pintype "tri_state"))
      (node (ref "R10") (pin "1") (pinfunction "1_1") (pintype "passive"))
    )
    (net (code "13") (name "Net-(IC1-QG)") (class "Default")
      (node (ref "IC1") (pin "6") (pinfunction "QG_6") (pintype "tri_state"))
      (node (ref "R11") (pin "1") (pinfunction "1_1") (pintype "passive"))
    )
    (net (code "14") (name "Net-(IC1-QH)") (class "Default")
      (node (ref "IC1") (pin "7") (pinfunction "QH_7") (pintype "tri_state"))
      (node (ref "R12") (pin "1") (pinfunction "1_1") (pintype "passive"))
    )
    (net (code "15") (name "Net-(IC1-QH*)") (class "Default")
      (node (ref "IC1") (pin "9") (pinfunction "QH*_9") (pintype "tri_state"))
      (node (ref "IC2") (pin "14") (pinfunction "SER_14") (pintype "input"))
    )
    (net (code "16") (name "Net-(IC2-QA)") (class "Default")
      (node (ref "IC2") (pin "15") (pinfunction "QA_15") (pintype "tri_state"))
      (node (ref "R13") (pin "1") (pinfunction "1_1") (pintype "passive"))
    )
    (net (code "17") (name "Net-(IC2-QB)") (class "Default")
      (node (ref "IC2") (pin "1") (pinfunction "QB_1") (pintype "tri_state"))
      (node (ref "R14") (pin "1") (pinfunction "1_1") (pintype "passive"))
    )
    (net (code "18") (name "Net-(IC2-QC)") (class "Default")
      (node (ref "IC2") (pin "2") (pinfunction "QC_2") (pintype "tri_state"))
      (node (ref "R15") (pin "1") (pinfunction "1_1") (pintype "passive"))
    )
    (net (code "19") (name "Net-(IC2-QD)") (class "Default")
      (node (ref "IC2") (pin "3") (pinfunction "QD_3") (pintype "tri_state"))
      (node (ref "R16") (pin "1") (pinfunction "1_1") (pintype "passive"))
    )
    (net (code "20") (name "Net-(IC2-QE)") (class "Default")
      (node (ref "IC2") (pin "4") (pinfunction "QE_4") (pintype "tri_state"))
      (node (ref "R17") (pin "1") (pinfunction "1_1") (pintype "passive"))
    )
    (net (code "21") (name "Net-(IC2-QF)") (class "Default")
      (node (ref "IC2") (pin "5") (pinfunction "QF_5") (pintype "tri_state"))
      (node (ref "R18") (pin "1") (pinfunction "1_1") (pintype "passive"))
    )
    (net (code "22") (name "Net-(IC2-QG)") (class "Default")
      (node (ref "IC2") (pin "6") (pinfunction "QG_6") (pintype "tri_state"))
      (node (ref "R19") (pin "1") (pinfunction "1_1") (pintype "passive"))
    )
    (net (code "23") (name "Net-(IC2-QH)") (class "Default")
      (node (ref "IC2") (pin "7") (pinfunction "QH_7") (pintype "tri_state"))
      (node (ref "R20") (pin "1") (pinfunction "1_1") (pintype "passive"))
    )
    (net (code "24") (name "Net-(IC2-QH*)") (class "Default")
      (node (ref "IC2") (pin "9") (pinfunction "QH*_9") (pintype "tri_state"))
      (node (ref "IC3") (pin "14") (pinfunction "SER_14") (pintype "input"))
    )
    (net (code "25") (name "Net-(IC3-QA)") (class "Default")
      (node (ref "IC3") (pin "15") (pinfunction "QA_15") (pintype "tri_state"))
      (node (ref "R21") (pin "1") (pinfunction "1_1") (pintype "passive"))
    )
    (net (code "26") (name "Net-(IC3-QB)") (class "Default")
      (node (ref "IC3") (pin "1") (pinfunction "QB_1") (pintype "tri_state"))
      (node (ref "R22") (pin "1") (pinfunction "1_1") (pintype "passive"))
    )
    (net (code "27") (name "Net-(IC3-QC)") (class "Default")
      (node (ref "IC3") (pin "2") (pinfunction "QC_2") (pintype "tri_state"))
      (node (ref "R23") (pin "1") (pinfunction "1_1") (pintype "passive"))
    )
    (net (code "28") (name "Net-(IC3-QD)") (class "Default")
      (node (ref "IC3") (pin "3") (pinfunction "QD_3") (pintype "tri_state"))
      (node (ref "R24") (pin "1") (pinfunction "1_1") (pintype "passive"))
    )
    (net (code "29") (name "Net-(IC3-QE)") (class "Default")
      (node (ref "IC3") (pin "4") (pinfunction "QE_4") (pintype "tri_state"))
      (node (ref "R25") (pin "1") (pinfunction "1_1") (pintype "passive"))
    )
    (net (code "30") (name "Net-(IC3-QF)") (class "Default")
      (node (ref "IC3") (pin "5") (pinfunction "QF_5") (pintype "tri_state"))
      (node (ref "R26") (pin "1") (pinfunction "1_1") (pintype "passive"))
    )
    (net (code "31") (name "Net-(IC3-QG)") (class "Default")
      (node (ref "IC3") (pin "6") (pinfunction "QG_6") (pintype "tri_state"))
      (node (ref "R27") (pin "1") (pinfunction "1_1") (pintype "passive"))
    )
    (net (code "32") (name "Net-(IC3-QH)") (class "Default")
      (node (ref "IC3") (pin "7") (pinfunction "QH_7") (pintype "tri_state"))
      (node (ref "R28") (pin "1") (pinfunction "1_1") (pintype "passive"))
    )
    (net (code "33") (name "Net-(IC3-QH*)") (class "Default")
      (node (ref "IC3") (pin "9") (pinfunction "QH*_9") (pintype "tri_state"))
      (node (ref "IC4") (pin "14") (pinfunction "SER_14") (pintype "input"))
    )
    (net (code "34") (name "Net-(IC4-QA)") (class "Default")
      (node (ref "IC4") (pin "15") (pinfunction "QA_15") (pintype "tri_state"))
      (node (ref "R29") (pin "1") (pinfunction "1_1") (pintype "passive"))
    )
    (net (code "35") (name "Net-(IC4-QB)") (class "Default")
      (node (ref "IC4") (pin "1") (pinfunction "QB_1") (pintype "tri_state"))
      (node (ref "R30") (pin "1") (pinfunction "1_1") (pintype "passive"))
    )
    (net (code "36") (name "Net-(IC4-QC)") (class "Default")
      (node (ref "IC4") (pin "2") (pinfunction "QC_2") (pintype "tri_state"))
      (node (ref "R31") (pin "1") (pinfunction "1_1") (pintype "passive"))
    )
    (net (code "37") (name "Net-(IC4-QD)") (class "Default")
      (node (ref "IC4") (pin "3") (pinfunction "QD_3") (pintype "tri_state"))
      (node (ref "R32") (pin "1") (pinfunction "1_1") (pintype "passive"))
    )
    (net (code "38") (name "Net-(IC4-QE)") (class "Default")
      (node (ref "IC4") (pin "4") (pinfunction "QE_4") (pintype "tri_state"))
      (node (ref "R33") (pin "1") (pinfunction "1_1") (pintype "passive"))
    )
    (net (code "39") (name "Net-(IC4-QF)") (class "Default")
      (node (ref "IC4") (pin "5") (pinfunction "QF_5") (pintype "tri_state"))
      (node (ref "R34") (pin "1") (pinfunction "1_1") (pintype "passive"))
    )
    (net (code "40") (name "Net-(IC4-QG)") (class "Default")
      (node (ref "IC4") (pin "6") (pinfunction "QG_6") (pintype "tri_state"))
      (node (ref "R35") (pin "1") (pinfunction "1_1") (pintype "passive"))
    )
    (net (code "41") (name "Net-(IC4-QH)") (class "Default")
      (node (ref "IC4") (pin "7") (pinfunction "QH_7") (pintype "tri_state"))
      (node (ref "R36") (pin "1") (pinfunction "1_1") (pintype "passive"))
    )
    (net (code "42") (name "Net-(IC4-QH*)") (class "Default")
      (node (ref "IC4") (pin "9") (pinfunction "QH*_9") (pintype "tri_state"))
      (node (ref "IC5") (pin "14") (pinfunction "SER_14") (pintype "input"))
    )
    (net (code "43") (name "Net-(IC5-QA)") (class "Default")
      (node (ref "IC5") (pin "15") (pinfunction "QA_15") (pintype "tri_state"))
      (node (ref "R37") (pin "1") (pinfunction "1_1") (pintype "passive"))
    )
    (net (code "44") (name "Net-(IC5-QB)") (class "Default")
      (node (ref "IC5") (pin "1") (pinfunction "QB_1") (pintype "tri_state"))
      (node (ref "R38") (pin "1") (pinfunction "1_1") (pintype "passive"))
    )
    (net (code "45") (name "Net-(IC5-QC)") (class "Default")
      (node (ref "IC5") (pin "2") (pinfunction "QC_2") (pintype "tri_state"))
      (node (ref "R39") (pin "1") (pinfunction "1_1") (pintype "passive"))
    )
    (net (code "46") (name "Net-(IC5-QD)") (class "Default")
      (node (ref "IC5") (pin "3") (pinfunction "QD_3") (pintype "tri_state"))
      (node (ref "R40") (pin "1") (pinfunction "1_1") (pintype "passive"))
    )
    (net (code "47") (name "Net-(IC5-QE)") (class "Default")
      (node (ref "IC5") (pin "4") (pinfunction "QE_4") (pintype "tri_state"))
      (node (ref "R41") (pin "1") (pinfunction "1_1") (pintype "passive"))
    )
    (net (code "48") (name "Net-(IC5-QF)") (class "Default")
      (node (ref "IC5") (pin "5") (pinfunction "QF_5") (pintype "tri_state"))
      (node (ref "R42") (pin "1") (pinfunction "1_1") (pintype "passive"))
    )
    (net (code "49") (name "Net-(IC5-QG)") (class "Default")
      (node (ref "IC5") (pin "6") (pinfunction "QG_6") (pintype "tri_state"))
      (node (ref "R43") (pin "1") (pinfunction "1_1") (pintype "passive"))
    )
    (net (code "50") (name "Net-(IC5-QH)") (class "Default")
      (node (ref "IC5") (pin "7") (pinfunction "QH_7") (pintype "tri_state"))
      (node (ref "R44") (pin "1") (pinfunction "1_1") (pintype "passive"))
    )
    (net (code "51") (name "Net-(IC5-QH*)") (class "Default")
      (node (ref "IC5") (pin "9") (pinfunction "QH*_9") (pintype "tri_state"))
      (node (ref "IC6") (pin "14") (pinfunction "SER_14") (pintype "input"))
    )
    (net (code "52") (name "Net-(IC6-QA)") (class "Default")
      (node (ref "IC6") (pin "15") (pinfunction "QA_15") (pintype "tri_state"))
      (node (ref "R45") (pin "1") (pinfunction "1_1") (pintype "passive"))
    )
    (net (code "53") (name "Net-(IC6-QB)") (class "Default")
      (node (ref "IC6") (pin "1") (pinfunction "QB_1") (pintype "tri_state"))
      (node (ref "R46") (pin "1") (pinfunction "1_1") (pintype "passive"))
    )
    (net (code "54") (name "Net-(IC6-QC)") (class "Default")
      (node (ref "IC6") (pin "2") (pinfunction "QC_2") (pintype "tri_state"))
      (node (ref "R47") (pin "1") (pinfunction "1_1") (pintype "passive"))
    )
    (net (code "55") (name "Net-(IC6-QD)") (class "Default")
      (node (ref "IC6") (pin "3") (pinfunction "QD_3") (pintype "tri_state"))
      (node (ref "R48") (pin "1") (pinfunction "1_1") (pintype "passive"))
    )
    (net (code "56") (name "Net-(IC6-QE)") (class "Default")
      (node (ref "IC6") (pin "4") (pinfunction "QE_4") (pintype "tri_state"))
      (node (ref "R49") (pin "1") (pinfunction "1_1") (pintype "passive"))
    )
    (net (code "57") (name "Net-(IC6-QF)") (class "Default")
      (node (ref "IC6") (pin "5") (pinfunction "QF_5") (pintype "tri_state"))
      (node (ref "R50") (pin "1") (pinfunction "1_1") (pintype "passive"))
    )
    (net (code "58") (name "Net-(IC6-QG)") (class "Default")
      (node (ref "IC6") (pin "6") (pinfunction "QG_6") (pintype "tri_state"))
      (node (ref "R51") (pin "1") (pinfunction "1_1") (pintype "passive"))
    )
    (net (code "59") (name "Net-(IC6-QH)") (class "Default")
      (node (ref "IC6") (pin "7") (pinfunction "QH_7") (pintype "tri_state"))
      (node (ref "R52") (pin "1") (pinfunction "1_1") (pintype "passive"))
    )
    (net (code "60") (name "Net-(IC6-QH*)") (class "Default")
      (node (ref "IC6") (pin "9") (pinfunction "QH*_9") (pintype "tri_state"))
      (node (ref "IC7") (pin "14") (pinfunction "SER_14") (pintype "input"))
    )
    (net (code "61") (name "Net-(IC7-QA)") (class "Default")
      (node (ref "IC7") (pin "15") (pinfunction "QA_15") (pintype "tri_state"))
      (node (ref "R53") (pin "1") (pinfunction "1_1") (pintype "passive"))
    )
    (net (code "62") (name "Net-(IC7-QB)") (class "Default")
      (node (ref "IC7") (pin "1") (pinfunction "QB_1") (pintype "tri_state"))
      (node (ref "R54") (pin "1") (pinfunction "1_1") (pintype "passive"))
    )
    (net (code "63") (name "Net-(IC7-QC)") (class "Default")
      (node (ref "IC7") (pin "2") (pinfunction "QC_2") (pintype "tri_state"))
      (node (ref "R55") (pin "1") (pinfunction "1_1") (pintype "passive"))
    )
    (net (code "64") (name "Net-(IC7-QD)") (class "Default")
      (node (ref "IC7") (pin "3") (pinfunction "QD_3") (pintype "tri_state"))
      (node (ref "R56") (pin "1") (pinfunction "1_1") (pintype "passive"))
    )
    (net (code "65") (name "Net-(IC7-QE)") (class "Default")
      (node (ref "IC7") (pin "4") (pinfunction "QE_4") (pintype "tri_state"))
      (node (ref "R57") (pin "1") (pinfunction "1_1") (pintype "passive"))
    )
    (net (code "66") (name "Net-(IC7-QF)") (class "Default")
      (node (ref "IC7") (pin "5") (pinfunction "QF_5") (pintype "tri_state"))
      (node (ref "R58") (pin "1") (pinfunction "1_1") (pintype "passive"))
    )
    (net (code "67") (name "Net-(IC7-QG)") (class "Default")
      (node (ref "IC7") (pin "6") (pinfunction "QG_6") (pintype "tri_state"))
      (node (ref "R59") (pin "1") (pinfunction "1_1") (pintype "passive"))
    )
    (net (code "68") (name "Net-(IC7-QH*)") (class "Default")
      (node (ref "IC7") (pin "9") (pinfunction "QH*_9") (pintype "tri_state"))
      (node (ref "IC8") (pin "14") (pinfunction "SER_14") (pintype "input"))
    )
    (net (code "69") (name "Net-(IC8-QA)") (class "Default")
      (node (ref "IC8") (pin "15") (pinfunction "QA_15") (pintype "tri_state"))
      (node (ref "R60") (pin "1") (pinfunction "1_1") (pintype "passive"))
    )
    (net (code "70") (name "Net-(IC8-QB)") (class "Default")
      (node (ref "IC8") (pin "1") (pinfunction "QB_1") (pintype "tri_state"))
      (node (ref "R61") (pin "1") (pinfunction "1_1") (pintype "passive"))
    )
    (net (code "71") (name "Net-(IC8-QC)") (class "Default")
      (node (ref "IC8") (pin "2") (pinfunction "QC_2") (pintype "tri_state"))
      (node (ref "R62") (pin "1") (pinfunction "1_1") (pintype "passive"))
    )
    (net (code "72") (name "Net-(IC8-QD)") (class "Default")
      (node (ref "IC8") (pin "3") (pinfunction "QD_3") (pintype "tri_state"))
      (node (ref "R63") (pin "1") (pinfunction "1_1") (pintype "passive"))
    )
    (net (code "73") (name "Net-(IC8-QE)") (class "Default")
      (node (ref "IC8") (pin "4") (pinfunction "QE_4") (pintype "tri_state"))
      (node (ref "R64") (pin "1") (pinfunction "1_1") (pintype "passive"))
    )
    (net (code "74") (name "Net-(IC8-QF)") (class "Default")
      (node (ref "IC8") (pin "5") (pinfunction "QF_5") (pintype "tri_state"))
      (node (ref "R65") (pin "1") (pinfunction "1_1") (pintype "passive"))
    )
    (net (code "75") (name "Net-(IC8-QG)") (class "Default")
      (node (ref "IC8") (pin "6") (pinfunction "QG_6") (pintype "tri_state"))
      (node (ref "R66") (pin "1") (pinfunction "1_1") (pintype "passive"))
    )
    (net (code "76") (name "Net-(IC8-QH*)") (class "Default")
      (node (ref "IC8") (pin "9") (pinfunction "QH*_9") (pintype "tri_state"))
      (node (ref "IC9") (pin "14") (pinfunction "SER_14") (pintype "input"))
    )
    (net (code "77") (name "Net-(IC9-QA)") (class "Default")
      (node (ref "IC9") (pin "15") (pinfunction "QA_15") (pintype "tri_state"))
      (node (ref "R67") (pin "1") (pinfunction "1_1") (pintype "passive"))
    )
    (net (code "78") (name "Net-(IC9-QB)") (class "Default")
      (node (ref "IC9") (pin "1") (pinfunction "QB_1") (pintype "tri_state"))
      (node (ref "R68") (pin "1") (pinfunction "1_1") (pintype "passive"))
    )
    (net (code "79") (name "Net-(IC9-QC)") (class "Default")
      (node (ref "IC9") (pin "2") (pinfunction "QC_2") (pintype "tri_state"))
      (node (ref "R69") (pin "1") (pinfunction "1_1") (pintype "passive"))
    )
    (net (code "80") (name "Net-(IC9-QD)") (class "Default")
      (node (ref "IC9") (pin "3") (pinfunction "QD_3") (pintype "tri_state"))
      (node (ref "R70") (pin "1") (pinfunction "1_1") (pintype "passive"))
    )
    (net (code "81") (name "Net-(IC9-QE)") (class "Default")
      (node (ref "IC9") (pin "4") (pinfunction "QE_4") (pintype "tri_state"))
      (node (ref "R71") (pin "1") (pinfunction "1_1") (pintype "passive"))
    )
    (net (code "82") (name "Net-(IC9-QF)") (class "Default")
      (node (ref "IC9") (pin "5") (pinfunction "QF_5") (pintype "tri_state"))
      (node (ref "R72") (pin "1") (pinfunction "1_1") (pintype "passive"))
    )
    (net (code "83") (name "Net-(IC9-QG)") (class "Default")
      (node (ref "IC9") (pin "6") (pinfunction "QG_6") (pintype "tri_state"))
      (node (ref "R73") (pin "1") (pinfunction "1_1") (pintype "passive"))
    )
    (net (code "84") (name "Net-(IC10-QA)") (class "Default")
      (node (ref "IC10") (pin "15") (pinfunction "QA_15") (pintype "tri_state"))
      (node (ref "R74") (pin "1") (pinfunction "1_1") (pintype "passive"))
    )
    (net (code "85") (name "Net-(IC10-QB)") (class "Default")
      (node (ref "IC10") (pin "1") (pinfunction "QB_1") (pintype "tri_state"))
      (node (ref "R75") (pin "1") (pinfunction "1_1") (pintype "passive"))
    )
    (net (code "86") (name "Net-(IC10-QC)") (class "Default")
      (node (ref "IC10") (pin "2") (pinfunction "QC_2") (pintype "tri_state"))
      (node (ref "R76") (pin "1") (pinfunction "1_1") (pintype "passive"))
    )
    (net (code "87") (name "Net-(IC10-QD)") (class "Default")
      (node (ref "IC10") (pin "3") (pinfunction "QD_3") (pintype "tri_state"))
      (node (ref "R77") (pin "1") (pinfunction "1_1") (pintype "passive"))
    )
    (net (code "88") (name "Net-(IC10-QE)") (class "Default")
      (node (ref "IC10") (pin "4") (pinfunction "QE_4") (pintype "tri_state"))
      (node (ref "R78") (pin "1") (pinfunction "1_1") (pintype "passive"))
    )
    (net (code "89") (name "Net-(IC10-QF)") (class "Default")
      (node (ref "IC10") (pin "5") (pinfunction "QF_5") (pintype "tri_state"))
      (node (ref "R79") (pin "1") (pinfunction "1_1") (pintype "passive"))
    )
    (net (code "90") (name "Net-(IC10-QG)") (class "Default")
      (node (ref "IC10") (pin "6") (pinfunction "QG_6") (pintype "tri_state"))
      (node (ref "R80") (pin "1") (pinfunction "1_1") (pintype "passive"))
    )
    (net (code "91") (name "Net-(IC10-QH*)") (class "Default")
      (node (ref "IC10") (pin "9") (pinfunction "QH*_9") (pintype "tri_state"))
      (node (ref "IC11") (pin "14") (pinfunction "SER_14") (pintype "input"))
    )
    (net (code "92") (name "Net-(IC10-SER)") (class "Default")
      (node (ref "IC10") (pin "14") (pinfunction "SER_14") (pintype "input"))
      (node (ref "IC9") (pin "9") (pinfunction "QH*_9") (pintype "tri_state"))
    )
    (net (code "93") (name "Net-(IC11-QA)") (class "Default")
      (node (ref "IC11") (pin "15") (pinfunction "QA_15") (pintype "tri_state"))
      (node (ref "R81") (pin "1") (pinfunction "1_1") (pintype "passive"))
    )
    (net (code "94") (name "Net-(IC11-QB)") (class "Default")
      (node (ref "IC11") (pin "1") (pinfunction "QB_1") (pintype "tri_state"))
      (node (ref "R82") (pin "1") (pinfunction "1_1") (pintype "passive"))
    )
    (net (code "95") (name "Net-(IC11-QC)") (class "Default")
      (node (ref "IC11") (pin "2") (pinfunction "QC_2") (pintype "tri_state"))
      (node (ref "R83") (pin "1") (pinfunction "1_1") (pintype "passive"))
    )
    (net (code "96") (name "Net-(IC11-QD)") (class "Default")
      (node (ref "IC11") (pin "3") (pinfunction "QD_3") (pintype "tri_state"))
      (node (ref "R84") (pin "1") (pinfunction "1_1") (pintype "passive"))
    )
    (net (code "97") (name "Net-(IC11-QE)") (class "Default")
      (node (ref "IC11") (pin "4") (pinfunction "QE_4") (pintype "tri_state"))
      (node (ref "R85") (pin "1") (pinfunction "1_1") (pintype "passive"))
    )
    (net (code "98") (name "Net-(IC11-QF)") (class "Default")
      (node (ref "IC11") (pin "5") (pinfunction "QF_5") (pintype "tri_state"))
      (node (ref "R86") (pin "1") (pinfunction "1_1") (pintype "passive"))
    )
    (net (code "99") (name "Net-(IC11-QG)") (class "Default")
      (node (ref "IC11") (pin "6") (pinfunction "QG_6") (pintype "tri_state"))
      (node (ref "R87") (pin "1") (pinfunction "1_1") (pintype "passive"))
    )
    (net (code "100") (name "Net-(IC11-QH*)") (class "Default")
      (node (ref "IC11") (pin "9") (pinfunction "QH*_9") (pintype "tri_state"))
      (node (ref "IC12") (pin "14") (pinfunction "SER_14") (pintype "input"))
    )
    (net (code "101") (name "Net-(IC12-QA)") (class "Default")
      (node (ref "IC12") (pin "15") (pinfunction "QA_15") (pintype "tri_state"))
      (node (ref "R88") (pin "1") (pinfunction "1_1") (pintype "passive"))
    )
    (net (code "102") (name "Net-(IC12-QB)") (class "Default")
      (node (ref "IC12") (pin "1") (pinfunction "QB_1") (pintype "tri_state"))
      (node (ref "R89") (pin "1") (pinfunction "1_1") (pintype "passive"))
    )
    (net (code "103") (name "Net-(IC12-QC)") (class "Default")
      (node (ref "IC12") (pin "2") (pinfunction "QC_2") (pintype "tri_state"))
      (node (ref "R90") (pin "1") (pinfunction "1_1") (pintype "passive"))
    )
    (net (code "104") (name "Net-(IC12-QD)") (class "Default")
      (node (ref "IC12") (pin "3") (pinfunction "QD_3") (pintype "tri_state"))
      (node (ref "R91") (pin "1") (pinfunction "1_1") (pintype "passive"))
    )
    (net (code "105") (name "Net-(IC12-QE)") (class "Default")
      (node (ref "IC12") (pin "4") (pinfunction "QE_4") (pintype "tri_state"))
      (node (ref "R92") (pin "1") (pinfunction "1_1") (pintype "passive"))
    )
    (net (code "106") (name "Net-(IC12-QF)") (class "Default")
      (node (ref "IC12") (pin "5") (pinfunction "QF_5") (pintype "tri_state"))
      (node (ref "R93") (pin "1") (pinfunction "1_1") (pintype "passive"))
    )
    (net (code "107") (name "Net-(IC12-QG)") (class "Default")
      (node (ref "IC12") (pin "6") (pinfunction "QG_6") (pintype "tri_state"))
      (node (ref "R94") (pin "1") (pinfunction "1_1") (pintype "passive"))
    )
    (net (code "108") (name "Net-(IC12-QH*)") (class "Default")
      (node (ref "IC12") (pin "9") (pinfunction "QH*_9") (pintype "tri_state"))
      (node (ref "IC13") (pin "14") (pinfunction "SER_14") (pintype "input"))
    )
    (net (code "109") (name "Net-(IC13-QA)") (class "Default")
      (node (ref "IC13") (pin "15") (pinfunction "QA_15") (pintype "tri_state"))
      (node (ref "R95") (pin "1") (pinfunction "1_1") (pintype "passive"))
    )
    (net (code "110") (name "Net-(IC13-QB)") (class "Default")
      (node (ref "IC13") (pin "1") (pinfunction "QB_1") (pintype "tri_state"))
      (node (ref "R96") (pin "1") (pinfunction "1_1") (pintype "passive"))
    )
    (net (code "111") (name "Net-(IC13-QC)") (class "Default")
      (node (ref "IC13") (pin "2") (pinfunction "QC_2") (pintype "tri_state"))
      (node (ref "R97") (pin "1") (pinfunction "1_1") (pintype "passive"))
    )
    (net (code "112") (name "Net-(IC13-QD)") (class "Default")
      (node (ref "IC13") (pin "3") (pinfunction "QD_3") (pintype "tri_state"))
      (node (ref "R98") (pin "1") (pinfunction "1_1") (pintype "passive"))
    )
    (net (code "113") (name "Net-(IC13-QE)") (class "Default")
      (node (ref "IC13") (pin "4") (pinfunction "QE_4") (pintype "tri_state"))
      (node (ref "R99") (pin "1") (pinfunction "1_1") (pintype "passive"))
    )
    (net (code "114") (name "Net-(IC13-QF)") (class "Default")
      (node (ref "IC13") (pin "5") (pinfunction "QF_5") (pintype "tri_state"))
      (node (ref "R100") (pin "1") (pinfunction "1_1") (pintype "passive"))
    )
    (net (code "115") (name "Net-(IC13-QG)") (class "Default")
      (node (ref "IC13") (pin "6") (pinfunction "QG_6") (pintype "tri_state"))
      (node (ref "R101") (pin "1") (pinfunction "1_1") (pintype "passive"))
    )
    (net (code "116") (name "Net-(IC13-QH)") (class "Default")
      (node (ref "IC13") (pin "7") (pinfunction "QH_7") (pintype "tri_state"))
      (node (ref "R126") (pin "1") (pinfunction "1_1") (pintype "passive"))
    )
    (net (code "117") (name "Net-(IC13-QH*)") (class "Default")
      (node (ref "IC13") (pin "9") (pinfunction "QH*_9") (pintype "tri_state"))
      (node (ref "IC14") (pin "14") (pinfunction "SER_14") (pintype "input"))
    )
    (net (code "118") (name "Net-(IC14-QA)") (class "Default")
      (node (ref "IC14") (pin "15") (pinfunction "QA_15") (pintype "tri_state"))
      (node (ref "R102") (pin "1") (pinfunction "1_1") (pintype "passive"))
    )
    (net (code "119") (name "Net-(IC14-QB)") (class "Default")
      (node (ref "IC14") (pin "1") (pinfunction "QB_1") (pintype "tri_state"))
      (node (ref "R103") (pin "1") (pinfunction "1_1") (pintype "passive"))
    )
    (net (code "120") (name "Net-(IC14-QC)") (class "Default")
      (node (ref "IC14") (pin "2") (pinfunction "QC_2") (pintype "tri_state"))
      (node (ref "R104") (pin "1") (pinfunction "1_1") (pintype "passive"))
    )
    (net (code "121") (name "Net-(IC14-QD)") (class "Default")
      (node (ref "IC14") (pin "3") (pinfunction "QD_3") (pintype "tri_state"))
      (node (ref "R105") (pin "1") (pinfunction "1_1") (pintype "passive"))
    )
    (net (code "122") (name "Net-(IC14-QE)") (class "Default")
      (node (ref "IC14") (pin "4") (pinfunction "QE_4") (pintype "tri_state"))
      (node (ref "R106") (pin "1") (pinfunction "1_1") (pintype "passive"))
    )
    (net (code "123") (name "Net-(IC14-QF)") (class "Default")
      (node (ref "IC14") (pin "5") (pinfunction "QF_5") (pintype "tri_state"))
      (node (ref "R107") (pin "1") (pinfunction "1_1") (pintype "passive"))
    )
    (net (code "124") (name "Net-(IC14-QG)") (class "Default")
      (node (ref "IC14") (pin "6") (pinfunction "QG_6") (pintype "tri_state"))
      (node (ref "R108") (pin "1") (pinfunction "1_1") (pintype "passive"))
    )
    (net (code "125") (name "Net-(IC14-QH)") (class "Default")
      (node (ref "IC14") (pin "7") (pinfunction "QH_7") (pintype "tri_state"))
      (node (ref "R125") (pin "1") (pinfunction "1_1") (pintype "passive"))
    )
    (net (code "126") (name "Net-(IC14-QH*)") (class "Default")
      (node (ref "IC14") (pin "9") (pinfunction "QH*_9") (pintype "tri_state"))
      (node (ref "IC15") (pin "14") (pinfunction "SER_14") (pintype "input"))
    )
    (net (code "127") (name "Net-(IC15-QA)") (class "Default")
      (node (ref "IC15") (pin "15") (pinfunction "QA_15") (pintype "tri_state"))
      (node (ref "R109") (pin "1") (pinfunction "1_1") (pintype "passive"))
    )
    (net (code "128") (name "Net-(IC15-QB)") (class "Default")
      (node (ref "IC15") (pin "1") (pinfunction "QB_1") (pintype "tri_state"))
      (node (ref "R110") (pin "1") (pinfunction "1_1") (pintype "passive"))
    )
    (net (code "129") (name "Net-(IC15-QC)") (class "Default")
      (node (ref "IC15") (pin "2") (pinfunction "QC_2") (pintype "tri_state"))
      (node (ref "R111") (pin "1") (pinfunction "1_1") (pintype "passive"))
    )
    (net (code "130") (name "Net-(IC15-QD)") (class "Default")
      (node (ref "IC15") (pin "3") (pinfunction "QD_3") (pintype "tri_state"))
      (node (ref "R112") (pin "1") (pinfunction "1_1") (pintype "passive"))
    )
    (net (code "131") (name "Net-(IC15-QE)") (class "Default")
      (node (ref "IC15") (pin "4") (pinfunction "QE_4") (pintype "tri_state"))
      (node (ref "R113") (pin "1") (pinfunction "1_1") (pintype "passive"))
    )
    (net (code "132") (name "Net-(IC15-QF)") (class "Default")
      (node (ref "IC15") (pin "5") (pinfunction "QF_5") (pintype "tri_state"))
      (node (ref "R114") (pin "1") (pinfunction "1_1") (pintype "passive"))
    )
    (net (code "133") (name "Net-(IC15-QG)") (class "Default")
      (node (ref "IC15") (pin "6") (pinfunction "QG_6") (pintype "tri_state"))
      (node (ref "R115") (pin "1") (pinfunction "1_1") (pintype "passive"))
    )
    (net (code "134") (name "Net-(IC15-QH)") (class "Default")
      (node (ref "IC15") (pin "7") (pinfunction "QH_7") (pintype "tri_state"))
      (node (ref "R124") (pin "1") (pinfunction "1_1") (pintype "passive"))
    )
    (net (code "135") (name "Net-(IC15-QH*)") (class "Default")
      (node (ref "IC15") (pin "9") (pinfunction "QH*_9") (pintype "tri_state"))
      (node (ref "IC16") (pin "14") (pinfunction "SER_14") (pintype "input"))
    )
    (net (code "136") (name "Net-(IC16-QA)") (class "Default")
      (node (ref "IC16") (pin "15") (pinfunction "QA_15") (pintype "tri_state"))
      (node (ref "R116") (pin "1") (pinfunction "1_1") (pintype "passive"))
    )
    (net (code "137") (name "Net-(IC16-QB)") (class "Default")
      (node (ref "IC16") (pin "1") (pinfunction "QB_1") (pintype "tri_state"))
      (node (ref "R117") (pin "1") (pinfunction "1_1") (pintype "passive"))
    )
    (net (code "138") (name "Net-(IC16-QC)") (class "Default")
      (node (ref "IC16") (pin "2") (pinfunction "QC_2") (pintype "tri_state"))
      (node (ref "R118") (pin "1") (pinfunction "1_1") (pintype "passive"))
    )
    (net (code "139") (name "Net-(IC16-QD)") (class "Default")
      (node (ref "IC16") (pin "3") (pinfunction "QD_3") (pintype "tri_state"))
      (node (ref "R119") (pin "1") (pinfunction "1_1") (pintype "passive"))
    )
    (net (code "140") (name "Net-(IC16-QE)") (class "Default")
      (node (ref "IC16") (pin "4") (pinfunction "QE_4") (pintype "tri_state"))
      (node (ref "R120") (pin "1") (pinfunction "1_1") (pintype "passive"))
    )
    (net (code "141") (name "Net-(IC16-QF)") (class "Default")
      (node (ref "IC16") (pin "5") (pinfunction "QF_5") (pintype "tri_state"))
      (node (ref "R121") (pin "1") (pinfunction "1_1") (pintype "passive"))
    )
    (net (code "142") (name "Net-(IC16-QG)") (class "Default")
      (node (ref "IC16") (pin "6") (pinfunction "QG_6") (pintype "tri_state"))
      (node (ref "R122") (pin "1") (pinfunction "1_1") (pintype "passive"))
    )
    (net (code "143") (name "Net-(IC16-QH)") (class "Default")
      (node (ref "IC16") (pin "7") (pinfunction "QH_7") (pintype "tri_state"))
      (node (ref "R123") (pin "1") (pinfunction "1_1") (pintype "passive"))
    )
    (net (code "144") (name "Net-(IC16-QH*)") (class "Default")
      (node (ref "IC16") (pin "9") (pinfunction "QH*_9") (pintype "tri_state"))
      (node (ref "J2") (pin "6") (pinfunction "6_6") (pintype "passive"))
    )
    (net (code "145") (name "Net-(LED9-C)") (class "Default")
      (node (ref "LED9") (pin "K") (pinfunction "C_K") (pintype "passive"))
      (node (ref "R126") (pin "2") (pinfunction "2_2") (pintype "passive"))
    )
    (net (code "146") (name "Net-(LED10-C)") (class "Default")
      (node (ref "LED10") (pin "K") (pinfunction "C_K") (pintype "passive"))
      (node (ref "R125") (pin "2") (pinfunction "2_2") (pintype "passive"))
    )
    (net (code "147") (name "Net-(LED11-C)") (class "Default")
      (node (ref "LED11") (pin "K") (pinfunction "C_K") (pintype "passive"))
      (node (ref "R124") (pin "2") (pinfunction "2_2") (pintype "passive"))
    )
    (net (code "148") (name "Net-(LED12-C)") (class "Default")
      (node (ref "LED12") (pin "K") (pinfunction "C_K") (pintype "passive"))
      (node (ref "R123") (pin "2") (pinfunction "2_2") (pintype "passive"))
    )
    (net (code "149") (name "Net-(R1-Pad2)") (class "Default")
      (node (ref "R1") (pin "2") (pinfunction "2_2") (pintype "passive"))
      (node (ref "U$6") (pin "A") (pinfunction "A_A") (pintype "passive"))
    )
    (net (code "150") (name "Net-(R2-Pad2)") (class "Default")
      (node (ref "R2") (pin "2") (pinfunction "2_2") (pintype "passive"))
      (node (ref "U$6") (pin "B") (pinfunction "B_B") (pintype "passive"))
    )
    (net (code "151") (name "Net-(R7-Pad2)") (class "Default")
      (node (ref "R7") (pin "2") (pinfunction "2_2") (pintype "passive"))
      (node (ref "U$6") (pin "C") (pinfunction "C_C") (pintype "passive"))
    )
    (net (code "152") (name "Net-(R8-Pad2)") (class "Default")
      (node (ref "R8") (pin "2") (pinfunction "2_2") (pintype "passive"))
      (node (ref "U$6") (pin "D") (pinfunction "D_D") (pintype "passive"))
    )
    (net (code "153") (name "Net-(R9-Pad2)") (class "Default")
      (node (ref "R9") (pin "2") (pinfunction "2_2") (pintype "passive"))
      (node (ref "U$6") (pin "E") (pinfunction "E_E") (pintype "passive"))
    )
    (net (code "154") (name "Net-(R10-Pad2)") (class "Default")
      (node (ref "R10") (pin "2") (pinfunction "2_2") (pintype "passive"))
      (node (ref "U$6") (pin "F") (pinfunction "F_F") (pintype "passive"))
    )
    (net (code "155") (name "Net-(R11-Pad2)") (class "Default")
      (node (ref "R11") (pin "2") (pinfunction "2_2") (pintype "passive"))
      (node (ref "U$6") (pin "G") (pinfunction "G_G") (pintype "passive"))
    )
    (net (code "156") (name "Net-(R12-Pad2)") (class "Default")
      (node (ref "R12") (pin "2") (pinfunction "2_2") (pintype "passive"))
      (node (ref "U$6") (pin "H") (pinfunction "H_H") (pintype "passive"))
    )
    (net (code "157") (name "Net-(R13-Pad2)") (class "Default")
      (node (ref "R13") (pin "2") (pinfunction "2_2") (pintype "passive"))
      (node (ref "U$6") (pin "K") (pinfunction "K_K") (pintype "passive"))
    )
    (net (code "158") (name "Net-(R14-Pad2)") (class "Default")
      (node (ref "R14") (pin "2") (pinfunction "2_2") (pintype "passive"))
      (node (ref "U$6") (pin "M") (pinfunction "M_M") (pintype "passive"))
    )
    (net (code "159") (name "Net-(R15-Pad2)") (class "Default")
      (node (ref "R15") (pin "2") (pinfunction "2_2") (pintype "passive"))
      (node (ref "U$6") (pin "N") (pinfunction "N_N") (pintype "passive"))
    )
    (net (code "160") (name "Net-(R16-Pad2)") (class "Default")
      (node (ref "R16") (pin "2") (pinfunction "2_2") (pintype "passive"))
      (node (ref "U$6") (pin "P") (pinfunction "P_P") (pintype "passive"))
    )
    (net (code "161") (name "Net-(R17-Pad2)") (class "Default")
      (node (ref "R17") (pin "2") (pinfunction "2_2") (pintype "passive"))
      (node (ref "U$6") (pin "R") (pinfunction "R_R") (pintype "passive"))
    )
    (net (code "162") (name "Net-(R18-Pad2)") (class "Default")
      (node (ref "R18") (pin "2") (pinfunction "2_2") (pintype "passive"))
      (node (ref "U$6") (pin "S") (pinfunction "S_S") (pintype "passive"))
    )
    (net (code "163") (name "Net-(R19-Pad2)") (class "Default")
      (node (ref "R19") (pin "2") (pinfunction "2_2") (pintype "passive"))
      (node (ref "U$6") (pin "T") (pinfunction "T_T") (pintype "passive"))
    )
    (net (code "164") (name "Net-(R20-Pad2)") (class "Default")
      (node (ref "R20") (pin "2") (pinfunction "2_2") (pintype "passive"))
      (node (ref "U$6") (pin "U") (pinfunction "U_U") (pintype "passive"))
    )
    (net (code "165") (name "Net-(R21-Pad2)") (class "Default")
      (node (ref "R21") (pin "2") (pinfunction "2_2") (pintype "passive"))
      (node (ref "U$7") (pin "A") (pinfunction "A_A") (pintype "passive"))
    )
    (net (code "166") (name "Net-(R22-Pad2)") (class "Default")
      (node (ref "R22") (pin "2") (pinfunction "2_2") (pintype "passive"))
      (node (ref "U$7") (pin "B") (pinfunction "B_B") (pintype "passive"))
    )
    (net (code "167") (name "Net-(R23-Pad2)") (class "Default")
      (node (ref "R23") (pin "2") (pinfunction "2_2") (pintype "passive"))
      (node (ref "U$7") (pin "C") (pinfunction "C_C") (pintype "passive"))
    )
    (net (code "168") (name "Net-(R24-Pad2)") (class "Default")
      (node (ref "R24") (pin "2") (pinfunction "2_2") (pintype "passive"))
      (node (ref "U$7") (pin "D") (pinfunction "D_D") (pintype "passive"))
    )
    (net (code "169") (name "Net-(R25-Pad2)") (class "Default")
      (node (ref "R25") (pin "2") (pinfunction "2_2") (pintype "passive"))
      (node (ref "U$7") (pin "E") (pinfunction "E_E") (pintype "passive"))
    )
    (net (code "170") (name "Net-(R26-Pad2)") (class "Default")
      (node (ref "R26") (pin "2") (pinfunction "2_2") (pintype "passive"))
      (node (ref "U$7") (pin "F") (pinfunction "F_F") (pintype "passive"))
    )
    (net (code "171") (name "Net-(R27-Pad2)") (class "Default")
      (node (ref "R27") (pin "2") (pinfunction "2_2") (pintype "passive"))
      (node (ref "U$7") (pin "G") (pinfunction "G_G") (pintype "passive"))
    )
    (net (code "172") (name "Net-(R28-Pad2)") (class "Default")
      (node (ref "R28") (pin "2") (pinfunction "2_2") (pintype "passive"))
      (node (ref "U$7") (pin "H") (pinfunction "H_H") (pintype "passive"))
    )
    (net (code "173") (name "Net-(R29-Pad2)") (class "Default")
      (node (ref "R29") (pin "2") (pinfunction "2_2") (pintype "passive"))
      (node (ref "U$7") (pin "K") (pinfunction "K_K") (pintype "passive"))
    )
    (net (code "174") (name "Net-(R30-Pad2)") (class "Default")
      (node (ref "R30") (pin "2") (pinfunction "2_2") (pintype "passive"))
      (node (ref "U$7") (pin "M") (pinfunction "M_M") (pintype "passive"))
    )
    (net (code "175") (name "Net-(R31-Pad2)") (class "Default")
      (node (ref "R31") (pin "2") (pinfunction "2_2") (pintype "passive"))
      (node (ref "U$7") (pin "N") (pinfunction "N_N") (pintype "passive"))
    )
    (net (code "176") (name "Net-(R32-Pad2)") (class "Default")
      (node (ref "R32") (pin "2") (pinfunction "2_2") (pintype "passive"))
      (node (ref "U$7") (pin "P") (pinfunction "P_P") (pintype "passive"))
    )
    (net (code "177") (name "Net-(R33-Pad2)") (class "Default")
      (node (ref "R33") (pin "2") (pinfunction "2_2") (pintype "passive"))
      (node (ref "U$7") (pin "R") (pinfunction "R_R") (pintype "passive"))
    )
    (net (code "178") (name "Net-(R34-Pad2)") (class "Default")
      (node (ref "R34") (pin "2") (pinfunction "2_2") (pintype "passive"))
      (node (ref "U$7") (pin "S") (pinfunction "S_S") (pintype "passive"))
    )
    (net (code "179") (name "Net-(R35-Pad2)") (class "Default")
      (node (ref "R35") (pin "2") (pinfunction "2_2") (pintype "passive"))
      (node (ref "U$7") (pin "T") (pinfunction "T_T") (pintype "passive"))
    )
    (net (code "180") (name "Net-(R36-Pad2)") (class "Default")
      (node (ref "R36") (pin "2") (pinfunction "2_2") (pintype "passive"))
      (node (ref "U$7") (pin "U") (pinfunction "U_U") (pintype "passive"))
    )
    (net (code "181") (name "Net-(R37-Pad2)") (class "Default")
      (node (ref "R37") (pin "2") (pinfunction "2_2") (pintype "passive"))
      (node (ref "U$8") (pin "A") (pinfunction "A_A") (pintype "passive"))
    )
    (net (code "182") (name "Net-(R38-Pad2)") (class "Default")
      (node (ref "R38") (pin "2") (pinfunction "2_2") (pintype "passive"))
      (node (ref "U$8") (pin "B") (pinfunction "B_B") (pintype "passive"))
    )
    (net (code "183") (name "Net-(R39-Pad2)") (class "Default")
      (node (ref "R39") (pin "2") (pinfunction "2_2") (pintype "passive"))
      (node (ref "U$8") (pin "C") (pinfunction "C_C") (pintype "passive"))
    )
    (net (code "184") (name "Net-(R40-Pad2)") (class "Default")
      (node (ref "R40") (pin "2") (pinfunction "2_2") (pintype "passive"))
      (node (ref "U$8") (pin "D") (pinfunction "D_D") (pintype "passive"))
    )
    (net (code "185") (name "Net-(R41-Pad2)") (class "Default")
      (node (ref "R41") (pin "2") (pinfunction "2_2") (pintype "passive"))
      (node (ref "U$8") (pin "E") (pinfunction "E_E") (pintype "passive"))
    )
    (net (code "186") (name "Net-(R42-Pad2)") (class "Default")
      (node (ref "R42") (pin "2") (pinfunction "2_2") (pintype "passive"))
      (node (ref "U$8") (pin "F") (pinfunction "F_F") (pintype "passive"))
    )
    (net (code "187") (name "Net-(R43-Pad2)") (class "Default")
      (node (ref "R43") (pin "2") (pinfunction "2_2") (pintype "passive"))
      (node (ref "U$8") (pin "G") (pinfunction "G_G") (pintype "passive"))
    )
    (net (code "188") (name "Net-(R44-Pad2)") (class "Default")
      (node (ref "R44") (pin "2") (pinfunction "2_2") (pintype "passive"))
      (node (ref "U$8") (pin "H") (pinfunction "H_H") (pintype "passive"))
    )
    (net (code "189") (name "Net-(R45-Pad2)") (class "Default")
      (node (ref "R45") (pin "2") (pinfunction "2_2") (pintype "passive"))
      (node (ref "U$8") (pin "K") (pinfunction "K_K") (pintype "passive"))
    )
    (net (code "190") (name "Net-(R46-Pad2)") (class "Default")
      (node (ref "R46") (pin "2") (pinfunction "2_2") (pintype "passive"))
      (node (ref "U$8") (pin "M") (pinfunction "M_M") (pintype "passive"))
    )
    (net (code "191") (name "Net-(R47-Pad2)") (class "Default")
      (node (ref "R47") (pin "2") (pinfunction "2_2") (pintype "passive"))
      (node (ref "U$8") (pin "N") (pinfunction "N_N") (pintype "passive"))
    )
    (net (code "192") (name "Net-(R48-Pad2)") (class "Default")
      (node (ref "R48") (pin "2") (pinfunction "2_2") (pintype "passive"))
      (node (ref "U$8") (pin "P") (pinfunction "P_P") (pintype "passive"))
    )
    (net (code "193") (name "Net-(R49-Pad2)") (class "Default")
      (node (ref "R49") (pin "2") (pinfunction "2_2") (pintype "passive"))
      (node (ref "U$8") (pin "R") (pinfunction "R_R") (pintype "passive"))
    )
    (net (code "194") (name "Net-(R50-Pad2)") (class "Default")
      (node (ref "R50") (pin "2") (pinfunction "2_2") (pintype "passive"))
      (node (ref "U$8") (pin "S") (pinfunction "S_S") (pintype "passive"))
    )
    (net (code "195") (name "Net-(R51-Pad2)") (class "Default")
      (node (ref "R51") (pin "2") (pinfunction "2_2") (pintype "passive"))
      (node (ref "U$8") (pin "T") (pinfunction "T_T") (pintype "passive"))
    )
    (net (code "196") (name "Net-(R52-Pad2)") (class "Default")
      (node (ref "R52") (pin "2") (pinfunction "2_2") (pintype "passive"))
      (node (ref "U$8") (pin "U") (pinfunction "U_U") (pintype "passive"))
    )
    (net (code "197") (name "Net-(U$1A-A)") (class "Default")
      (node (ref "R53") (pin "2") (pinfunction "2_2") (pintype "passive"))
      (node (ref "U$1") (pin "1A") (pinfunction "A_1A") (pintype "bidirectional"))
    )
    (net (code "198") (name "Net-(U$1A-B)") (class "Default")
      (node (ref "R54") (pin "2") (pinfunction "2_2") (pintype "passive"))
      (node (ref "U$1") (pin "1B") (pinfunction "B_1B") (pintype "bidirectional"))
    )
    (net (code "199") (name "Net-(U$1A-C)") (class "Default")
      (node (ref "R55") (pin "2") (pinfunction "2_2") (pintype "passive"))
      (node (ref "U$1") (pin "1C") (pinfunction "C_1C") (pintype "bidirectional"))
    )
    (net (code "200") (name "Net-(U$1A-D)") (class "Default")
      (node (ref "R56") (pin "2") (pinfunction "2_2") (pintype "passive"))
      (node (ref "U$1") (pin "1D") (pinfunction "D_1D") (pintype "bidirectional"))
    )
    (net (code "201") (name "Net-(U$1A-E)") (class "Default")
      (node (ref "R57") (pin "2") (pinfunction "2_2") (pintype "passive"))
      (node (ref "U$1") (pin "1E") (pinfunction "E_1E") (pintype "bidirectional"))
    )
    (net (code "202") (name "Net-(U$1A-F)") (class "Default")
      (node (ref "R58") (pin "2") (pinfunction "2_2") (pintype "passive"))
      (node (ref "U$1") (pin "1F") (pinfunction "F_1F") (pintype "bidirectional"))
    )
    (net (code "203") (name "Net-(U$1A-G)") (class "Default")
      (node (ref "R59") (pin "2") (pinfunction "2_2") (pintype "passive"))
      (node (ref "U$1") (pin "1G") (pinfunction "G_1G") (pintype "bidirectional"))
    )
    (net (code "204") (name "Net-(U$1B-A)") (class "Default")
      (node (ref "R60") (pin "2") (pinfunction "2_2") (pintype "passive"))
      (node (ref "U$1") (pin "2A") (pinfunction "A_2A") (pintype "bidirectional"))
    )
    (net (code "205") (name "Net-(U$1B-B)") (class "Default")
      (node (ref "R61") (pin "2") (pinfunction "2_2") (pintype "passive"))
      (node (ref "U$1") (pin "2B") (pinfunction "B_2B") (pintype "bidirectional"))
    )
    (net (code "206") (name "Net-(U$1B-C)") (class "Default")
      (node (ref "R62") (pin "2") (pinfunction "2_2") (pintype "passive"))
      (node (ref "U$1") (pin "2C") (pinfunction "C_2C") (pintype "bidirectional"))
    )
    (net (code "207") (name "Net-(U$1B-D)") (class "Default")
      (node (ref "R63") (pin "2") (pinfunction "2_2") (pintype "passive"))
      (node (ref "U$1") (pin "2D") (pinfunction "D_2D") (pintype "bidirectional"))
    )
    (net (code "208") (name "Net-(U$1B-E)") (class "Default")
      (node (ref "R64") (pin "2") (pinfunction "2_2") (pintype "passive"))
      (node (ref "U$1") (pin "2E") (pinfunction "E_2E") (pintype "bidirectional"))
    )
    (net (code "209") (name "Net-(U$1B-F)") (class "Default")
      (node (ref "R65") (pin "2") (pinfunction "2_2") (pintype "passive"))
      (node (ref "U$1") (pin "2F") (pinfunction "F_2F") (pintype "bidirectional"))
    )
    (net (code "210") (name "Net-(U$1B-G)") (class "Default")
      (node (ref "R66") (pin "2") (pinfunction "2_2") (pintype "passive"))
      (node (ref "U$1") (pin "2G") (pinfunction "G_2G") (pintype "bidirectional"))
    )
    (net (code "211") (name "Net-(U$2A-A)") (class "Default")
      (node (ref "R67") (pin "2") (pinfunction "2_2") (pintype "passive"))
      (node (ref "U$2") (pin "1A") (pinfunction "A_1A") (pintype "bidirectional"))
    )
    (net (code "212") (name "Net-(U$2A-B)") (class "Default")
      (node (ref "R68") (pin "2") (pinfunction "2_2") (pintype "passive"))
      (node (ref "U$2") (pin "1B") (pinfunction "B_1B") (pintype "bidirectional"))
    )
    (net (code "213") (name "Net-(U$2A-C)") (class "Default")
      (node (ref "R69") (pin "2") (pinfunction "2_2") (pintype "passive"))
      (node (ref "U$2") (pin "1C") (pinfunction "C_1C") (pintype "bidirectional"))
    )
    (net (code "214") (name "Net-(U$2A-D)") (class "Default")
      (node (ref "R70") (pin "2") (pinfunction "2_2") (pintype "passive"))
      (node (ref "U$2") (pin "1D") (pinfunction "D_1D") (pintype "bidirectional"))
    )
    (net (code "215") (name "Net-(U$2A-E)") (class "Default")
      (node (ref "R71") (pin "2") (pinfunction "2_2") (pintype "passive"))
      (node (ref "U$2") (pin "1E") (pinfunction "E_1E") (pintype "bidirectional"))
    )
    (net (code "216") (name "Net-(U$2A-F)") (class "Default")
      (node (ref "R72") (pin "2") (pinfunction "2_2") (pintype "passive"))
      (node (ref "U$2") (pin "1F") (pinfunction "F_1F") (pintype "bidirectional"))
    )
    (net (code "217") (name "Net-(U$2A-G)") (class "Default")
      (node (ref "R73") (pin "2") (pinfunction "2_2") (pintype "passive"))
      (node (ref "U$2") (pin "1G") (pinfunction "G_1G") (pintype "bidirectional"))
    )
    (net (code "218") (name "Net-(U$2B-A)") (class "Default")
      (node (ref "R74") (pin "2") (pinfunction "2_2") (pintype "passive"))
      (node (ref "U$2") (pin "2A") (pinfunction "A_2A") (pintype "bidirectional"))
    )
    (net (code "219") (name "Net-(U$2B-B)") (class "Default")
      (node (ref "R75") (pin "2") (pinfunction "2_2") (pintype "passive"))
      (node (ref "U$2") (pin "2B") (pinfunction "B_2B") (pintype "bidirectional"))
    )
    (net (code "220") (name "Net-(U$2B-C)") (class "Default")
      (node (ref "R76") (pin "2") (pinfunction "2_2") (pintype "passive"))
      (node (ref "U$2") (pin "2C") (pinfunction "C_2C") (pintype "bidirectional"))
    )
    (net (code "221") (name "Net-(U$2B-D)") (class "Default")
      (node (ref "R77") (pin "2") (pinfunction "2_2") (pintype "passive"))
      (node (ref "U$2") (pin "2D") (pinfunction "D_2D") (pintype "bidirectional"))
    )
    (net (code "222") (name "Net-(U$2B-E)") (class "Default")
      (node (ref "R78") (pin "2") (pinfunction "2_2") (pintype "passive"))
      (node (ref "U$2") (pin "2E") (pinfunction "E_2E") (pintype "bidirectional"))
    )
    (net (code "223") (name "Net-(U$2B-F)") (class "Default")
      (node (ref "R79") (pin "2") (pinfunction "2_2") (pintype "passive"))
      (node (ref "U$2") (pin "2F") (pinfunction "F_2F") (pintype "bidirectional"))
    )
    (net (code "224") (name "Net-(U$2B-G)") (class "Default")
      (node (ref "R80") (pin "2") (pinfunction "2_2") (pintype "passive"))
      (node (ref "U$2") (pin "2G") (pinfunction "G_2G") (pintype "bidirectional"))
    )
    (net (code "225") (name "Net-(U$3A-A)") (class "Default")
      (node (ref "R81") (pin "2") (pinfunction "2_2") (pintype "passive"))
      (node (ref "U$3") (pin "1A") (pinfunction "A_1A") (pintype "bidirectional"))
    )
    (net (code "226") (name "Net-(U$3A-B)") (class "Default")
      (node (ref "R82") (pin "2") (pinfunction "2_2") (pintype "passive"))
      (node (ref "U$3") (pin "1B") (pinfunction "B_1B") (pintype "bidirectional"))
    )
    (net (code "227") (name "Net-(U$3A-C)") (class "Default")
      (node (ref "R83") (pin "2") (pinfunction "2_2") (pintype "passive"))
      (node (ref "U$3") (pin "1C") (pinfunction "C_1C") (pintype "bidirectional"))
    )
    (net (code "228") (name "Net-(U$3A-D)") (class "Default")
      (node (ref "R84") (pin "2") (pinfunction "2_2") (pintype "passive"))
      (node (ref "U$3") (pin "1D") (pinfunction "D_1D") (pintype "bidirectional"))
    )
    (net (code "229") (name "Net-(U$3A-E)") (class "Default")
      (node (ref "R85") (pin "2") (pinfunction "2_2") (pintype "passive"))
      (node (ref "U$3") (pin "1E") (pinfunction "E_1E") (pintype "bidirectional"))
    )
    (net (code "230") (name "Net-(U$3A-F)") (class "Default")
      (node (ref "R86") (pin "2") (pinfunction "2_2") (pintype "passive"))
      (node (ref "U$3") (pin "1F") (pinfunction "F_1F") (pintype "bidirectional"))
    )
    (net (code "231") (name "Net-(U$3A-G)") (class "Default")
      (node (ref "R87") (pin "2") (pinfunction "2_2") (pintype "passive"))
      (node (ref "U$3") (pin "1G") (pinfunction "G_1G") (pintype "bidirectional"))
    )
    (net (code "232") (name "Net-(U$3B-A)") (class "Default")
      (node (ref "R88") (pin "2") (pinfunction "2_2") (pintype "passive"))
      (node (ref "U$3") (pin "2A") (pinfunction "A_2A") (pintype "bidirectional"))
    )
    (net (code "233") (name "Net-(U$3B-B)") (class "Default")
      (node (ref "R89") (pin "2") (pinfunction "2_2") (pintype "passive"))
      (node (ref "U$3") (pin "2B") (pinfunction "B_2B") (pintype "bidirectional"))
    )
    (net (code "234") (name "Net-(U$3B-C)") (class "Default")
      (node (ref "R90") (pin "2") (pinfunction "2_2") (pintype "passive"))
      (node (ref "U$3") (pin "2C") (pinfunction "C_2C") (pintype "bidirectional"))
    )
    (net (code "235") (name "Net-(U$3B-D)") (class "Default")
      (node (ref "R91") (pin "2") (pinfunction "2_2") (pintype "passive"))
      (node (ref "U$3") (pin "2D") (pinfunction "D_2D") (pintype "bidirectional"))
    )
    (net (code "236") (name "Net-(U$3B-E)") (class "Default")
      (node (ref "R92") (pin "2") (pinfunction "2_2") (pintype "passive"))
      (node (ref "U$3") (pin "2E") (pinfunction "E_2E") (pintype "bidirectional"))
    )
    (net (code "237") (name "Net-(U$3B-F)") (class "Default")
      (node (ref "R93") (pin "2") (pinfunction "2_2") (pintype "passive"))
      (node (ref "U$3") (pin "2F") (pinfunction "F_2F") (pintype "bidirectional"))
    )
    (net (code "238") (name "Net-(U$3B-G)") (class "Default")
      (node (ref "R94") (pin "2") (pinfunction "2_2") (pintype "passive"))
      (node (ref "U$3") (pin "2G") (pinfunction "G_2G") (pintype "bidirectional"))
    )
    (net (code "239") (name "Net-(U$4A-A)") (class "Default")
      (node (ref "R95") (pin "2") (pinfunction "2_2") (pintype "passive"))
      (node (ref "U$4") (pin "1A") (pinfunction "A_1A") (pintype "bidirectional"))
    )
    (net (code "240") (name "Net-(U$4A-B)") (class "Default")
      (node (ref "R96") (pin "2") (pinfunction "2_2") (pintype "passive"))
      (node (ref "U$4") (pin "1B") (pinfunction "B_1B") (pintype "bidirectional"))
    )
    (net (code "241") (name "Net-(U$4A-C)") (class "Default")
      (node (ref "R97") (pin "2") (pinfunction "2_2") (pintype "passive"))
      (node (ref "U$4") (pin "1C") (pinfunction "C_1C") (pintype "bidirectional"))
    )
    (net (code "242") (name "Net-(U$4A-D)") (class "Default")
      (node (ref "R98") (pin "2") (pinfunction "2_2") (pintype "passive"))
      (node (ref "U$4") (pin "1D") (pinfunction "D_1D") (pintype "bidirectional"))
    )
    (net (code "243") (name "Net-(U$4A-E)") (class "Default")
      (node (ref "R99") (pin "2") (pinfunction "2_2") (pintype "passive"))
      (node (ref "U$4") (pin "1E") (pinfunction "E_1E") (pintype "bidirectional"))
    )
    (net (code "244") (name "Net-(U$4A-F)") (class "Default")
      (node (ref "R100") (pin "2") (pinfunction "2_2") (pintype "passive"))
      (node (ref "U$4") (pin "1F") (pinfunction "F_1F") (pintype "bidirectional"))
    )
    (net (code "245") (name "Net-(U$4A-G)") (class "Default")
      (node (ref "R101") (pin "2") (pinfunction "2_2") (pintype "passive"))
      (node (ref "U$4") (pin "1G") (pinfunction "G_1G") (pintype "bidirectional"))
    )
    (net (code "246") (name "Net-(U$4B-A)") (class "Default")
      (node (ref "R102") (pin "2") (pinfunction "2_2") (pintype "passive"))
      (node (ref "U$4") (pin "2A") (pinfunction "A_2A") (pintype "bidirectional"))
    )
    (net (code "247") (name "Net-(U$4B-B)") (class "Default")
      (node (ref "R103") (pin "2") (pinfunction "2_2") (pintype "passive"))
      (node (ref "U$4") (pin "2B") (pinfunction "B_2B") (pintype "bidirectional"))
    )
    (net (code "248") (name "Net-(U$4B-C)") (class "Default")
      (node (ref "R104") (pin "2") (pinfunction "2_2") (pintype "passive"))
      (node (ref "U$4") (pin "2C") (pinfunction "C_2C") (pintype "bidirectional"))
    )
    (net (code "249") (name "Net-(U$4B-D)") (class "Default")
      (node (ref "R105") (pin "2") (pinfunction "2_2") (pintype "passive"))
      (node (ref "U$4") (pin "2D") (pinfunction "D_2D") (pintype "bidirectional"))
    )
    (net (code "250") (name "Net-(U$4B-E)") (class "Default")
      (node (ref "R106") (pin "2") (pinfunction "2_2") (pintype "passive"))
      (node (ref "U$4") (pin "2E") (pinfunction "E_2E") (pintype "bidirectional"))
    )
    (net (code "251") (name "Net-(U$4B-F)") (class "Default")
      (node (ref "R107") (pin "2") (pinfunction "2_2") (pintype "passive"))
      (node (ref "U$4") (pin "2F") (pinfunction "F_2F") (pintype "bidirectional"))
    )
    (net (code "252") (name "Net-(U$4B-G)") (class "Default")
      (node (ref "R108") (pin "2") (pinfunction "2_2") (pintype "passive"))
      (node (ref "U$4") (pin "2G") (pinfunction "G_2G") (pintype "bidirectional"))
    )
    (net (code "253") (name "Net-(U$5A-A)") (class "Default")
      (node (ref "R109") (pin "2") (pinfunction "2_2") (pintype "passive"))
      (node (ref "U$5") (pin "1A") (pinfunction "A_1A") (pintype "bidirectional"))
    )
    (net (code "254") (name "Net-(U$5A-B)") (class "Default")
      (node (ref "R110") (pin "2") (pinfunction "2_2") (pintype "passive"))
      (node (ref "U$5") (pin "1B") (pinfunction "B_1B") (pintype "bidirectional"))
    )
    (net (code "255") (name "Net-(U$5A-C)") (class "Default")
      (node (ref "R111") (pin "2") (pinfunction "2_2") (pintype "passive"))
      (node (ref "U$5") (pin "1C") (pinfunction "C_1C") (pintype "bidirectional"))
    )
    (net (code "256") (name "Net-(U$5A-D)") (class "Default")
      (node (ref "R112") (pin "2") (pinfunction "2_2") (pintype "passive"))
      (node (ref "U$5") (pin "1D") (pinfunction "D_1D") (pintype "bidirectional"))
    )
    (net (code "257") (name "Net-(U$5A-E)") (class "Default")
      (node (ref "R113") (pin "2") (pinfunction "2_2") (pintype "passive"))
      (node (ref "U$5") (pin "1E") (pinfunction "E_1E") (pintype "bidirectional"))
    )
    (net (code "258") (name "Net-(U$5A-F)") (class "Default")
      (node (ref "R114") (pin "2") (pinfunction "2_2") (pintype "passive"))
      (node (ref "U$5") (pin "1F") (pinfunction "F_1F") (pintype "bidirectional"))
    )
    (net (code "259") (name "Net-(U$5A-G)") (class "Default")
      (node (ref "R115") (pin "2") (pinfunction "2_2") (pintype "passive"))
      (node (ref "U$5") (pin "1G") (pinfunction "G_1G") (pintype "bidirectional"))
    )
    (net (code "260") (name "Net-(U$5B-A)") (class "Default")
      (node (ref "R116") (pin "2") (pinfunction "2_2") (pintype "passive"))
      (node (ref "U$5") (pin "2A") (pinfunction "A_2A") (pintype "bidirectional"))
    )
    (net (code "261") (name "Net-(U$5B-B)") (class "Default")
      (node (ref "R117") (pin "2") (pinfunction "2_2") (pintype "passive"))
      (node (ref "U$5") (pin "2B") (pinfunction "B_2B") (pintype "bidirectional"))
    )
    (net (code "262") (name "Net-(U$5B-C)") (class "Default")
      (node (ref "R118") (pin "2") (pinfunction "2_2") (pintype "passive"))
      (node (ref "U$5") (pin "2C") (pinfunction "C_2C") (pintype "bidirectional"))
    )
    (net (code "263") (name "Net-(U$5B-D)") (class "Default")
      (node (ref "R119") (pin "2") (pinfunction "2_2") (pintype "passive"))
      (node (ref "U$5") (pin "2D") (pinfunction "D_2D") (pintype "bidirectional"))
    )
    (net (code "264") (name "Net-(U$5B-E)") (class "Default")
      (node (ref "R120") (pin "2") (pinfunction "2_2") (pintype "passive"))
      (node (ref "U$5") (pin "2E") (pinfunction "E_2E") (pintype "bidirectional"))
    )
    (net (code "265") (name "Net-(U$5B-F)") (class "Default")
      (node (ref "R121") (pin "2") (pinfunction "2_2") (pintype "passive"))
      (node (ref "U$5") (pin "2F") (pinfunction "F_2F") (pintype "bidirectional"))
    )
    (net (code "266") (name "Net-(U$5B-G)") (class "Default")
      (node (ref "R122") (pin "2") (pinfunction "2_2") (pintype "passive"))
      (node (ref "U$5") (pin "2G") (pinfunction "G_2G") (pintype "bidirectional"))
    )
    (net (code "267") (name "VCC") (class "Default")
      (node (ref "C1") (pin "1") (pinfunction "1_1") (pintype "passive"))
      (node (ref "C10") (pin "1") (pinfunction "1_1") (pintype "passive"))
      (node (ref "C11") (pin "1") (pinfunction "1_1") (pintype "passive"))
      (node (ref "C12") (pin "1") (pinfunction "1_1") (pintype "passive"))
      (node (ref "C13") (pin "1") (pinfunction "1_1") (pintype "passive"))
      (node (ref "C14") (pin "1") (pinfunction "1_1") (pintype "passive"))
      (node (ref "C15") (pin "1") (pinfunction "1_1") (pintype "passive"))
      (node (ref "C16") (pin "1") (pinfunction "1_1") (pintype "passive"))
      (node (ref "C17") (pin "+") (pinfunction "+_+") (pintype "passive"))
      (node (ref "C2") (pin "1") (pinfunction "1_1") (pintype "passive"))
      (node (ref "C3") (pin "1") (pinfunction "1_1") (pintype "passive"))
      (node (ref "C4") (pin "1") (pinfunction "1_1") (pintype "passive"))
      (node (ref "C5") (pin "1") (pinfunction "1_1") (pintype "passive"))
      (node (ref "C6") (pin "1") (pinfunction "1_1") (pintype "passive"))
      (node (ref "C7") (pin "1") (pinfunction "1_1") (pintype "passive"))
      (node (ref "C8") (pin "1") (pinfunction "1_1") (pintype "passive"))
      (node (ref "C9") (pin "1") (pinfunction "1_1") (pintype "passive"))
      (node (ref "IC1") (pin "16") (pinfunction "VCC_16") (pintype "power_in"))
      (node (ref "IC10") (pin "16") (pinfunction "VCC_16") (pintype "power_in"))
      (node (ref "IC11") (pin "16") (pinfunction "VCC_16") (pintype "power_in"))
      (node (ref "IC12") (pin "16") (pinfunction "VCC_16") (pintype "power_in"))
      (node (ref "IC13") (pin "16") (pinfunction "VCC_16") (pintype "power_in"))
      (node (ref "IC14") (pin "16") (pinfunction "VCC_16") (pintype "power_in"))
      (node (ref "IC15") (pin "16") (pinfunction "VCC_16") (pintype "power_in"))
      (node (ref "IC16") (pin "16") (pinfunction "VCC_16") (pintype "power_in"))
      (node (ref "IC2") (pin "16") (pinfunction "VCC_16") (pintype "power_in"))
      (node (ref "IC3") (pin "16") (pinfunction "VCC_16") (pintype "power_in"))
      (node (ref "IC4") (pin "16") (pinfunction "VCC_16") (pintype "power_in"))
      (node (ref "IC5") (pin "16") (pinfunction "VCC_16") (pintype "power_in"))
      (node (ref "IC6") (pin "16") (pinfunction "VCC_16") (pintype "power_in"))
      (node (ref "IC7") (pin "16") (pinfunction "VCC_16") (pintype "power_in"))
      (node (ref "IC8") (pin "16") (pinfunction "VCC_16") (pintype "power_in"))
      (node (ref "IC9") (pin "16") (pinfunction "VCC_16") (pintype "power_in"))
      (node (ref "J1") (pin "7") (pinfunction "7_7") (pintype "passive"))
      (node (ref "J2") (pin "7") (pinfunction "7_7") (pintype "passive"))
      (node (ref "LED10") (pin "A") (pinfunction "A_A") (pintype "passive"))
      (node (ref "LED11") (pin "A") (pinfunction "A_A") (pintype "passive"))
      (node (ref "LED12") (pin "A") (pinfunction "A_A") (pintype "passive"))
      (node (ref "LED9") (pin "A") (pinfunction "A_A") (pintype "passive"))
      (node (ref "U$1") (pin "1ANODE+") (pinfunction "COM/ANODE+_1ANODE+") (pintype "bidirectional"))
      (node (ref "U$1") (pin "2ANODE+") (pinfunction "COM/ANODE+_2ANODE+") (pintype "bidirectional"))
      (node (ref "U$2") (pin "1ANODE+") (pinfunction "COM/ANODE+_1ANODE+") (pintype "bidirectional"))
      (node (ref "U$2") (pin "2ANODE+") (pinfunction "COM/ANODE+_2ANODE+") (pintype "bidirectional"))
      (node (ref "U$3") (pin "1ANODE+") (pinfunction "COM/ANODE+_1ANODE+") (pintype "bidirectional"))
      (node (ref "U$3") (pin "2ANODE+") (pinfunction "COM/ANODE+_2ANODE+") (pintype "bidirectional"))
      (node (ref "U$4") (pin "1ANODE+") (pinfunction "COM/ANODE+_1ANODE+") (pintype "bidirectional"))
      (node (ref "U$4") (pin "2ANODE+") (pinfunction "COM/ANODE+_2ANODE+") (pintype "bidirectional"))
      (node (ref "U$5") (pin "1ANODE+") (pinfunction "COM/ANODE+_1ANODE+") (pintype "bidirectional"))
      (node (ref "U$5") (pin "2ANODE+") (pinfunction "COM/ANODE+_2ANODE+") (pintype "bidirectional"))
    )
    (net (code "268") (name "unconnected-(IC7-QH-Pad7)") (class "Default")
      (node (ref "IC7") (pin "7") (pinfunction "QH_7") (pintype "tri_state"))
    )
    (net (code "269") (name "unconnected-(IC8-QH-Pad7)") (class "Default")
      (node (ref "IC8") (pin "7") (pinfunction "QH_7") (pintype "tri_state"))
    )
    (net (code "270") (name "unconnected-(IC9-QH-Pad7)") (class "Default")
      (node (ref "IC9") (pin "7") (pinfunction "QH_7") (pintype "tri_state"))
    )
    (net (code "271") (name "unconnected-(IC10-QH-Pad7)") (class "Default")
      (node (ref "IC10") (pin "7") (pinfunction "QH_7") (pintype "tri_state"))
    )
    (net (code "272") (name "unconnected-(IC11-QH-Pad7)") (class "Default")
      (node (ref "IC11") (pin "7") (pinfunction "QH_7") (pintype "tri_state"))
    )
    (net (code "273") (name "unconnected-(IC12-QH-Pad7)") (class "Default")
      (node (ref "IC12") (pin "7") (pinfunction "QH_7") (pintype "tri_state"))
    )
    (net (code "274") (name "unconnected-(U$6-PadDP)") (class "Default")
      (node (ref "U$6") (pin "DP") (pinfunction "DP_DP") (pintype "passive"))
    )
    (net (code "275") (name "unconnected-(U$7-PadDP)") (class "Default")
      (node (ref "U$7") (pin "DP") (pinfunction "DP_DP") (pintype "passive"))
    )
    (net (code "276") (name "unconnected-(U$8-PadDP)") (class "Default")
      (node (ref "U$8") (pin "DP") (pinfunction "DP_DP") (pintype "passive"))
    )
  )
)
